# FPGA.net
KiCad netlist of a schematic drawn in Altium Designer
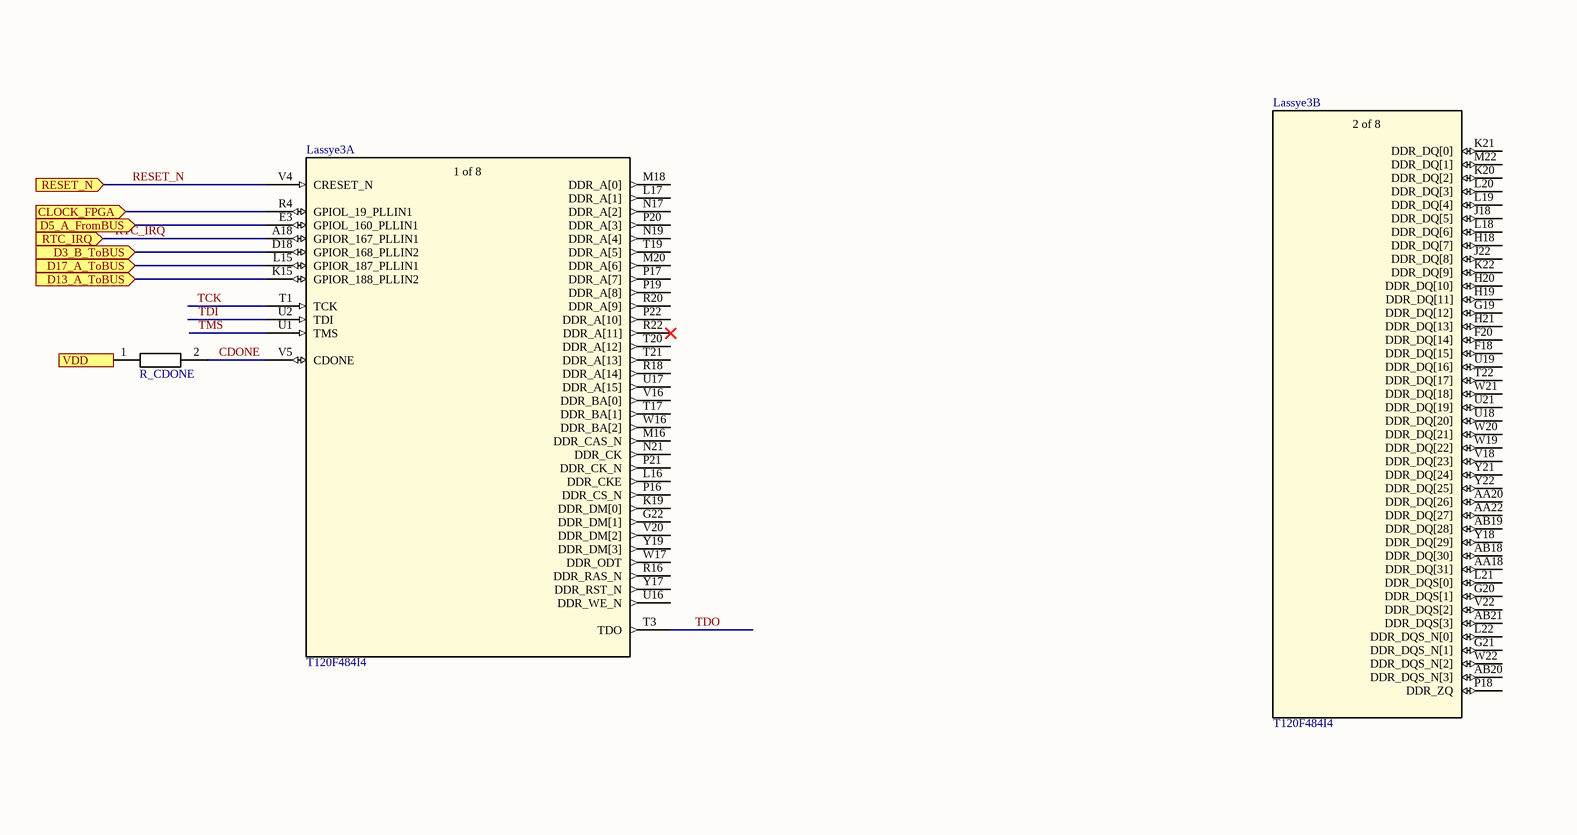
[diagram p0: FPGA.SchDoc, top left]
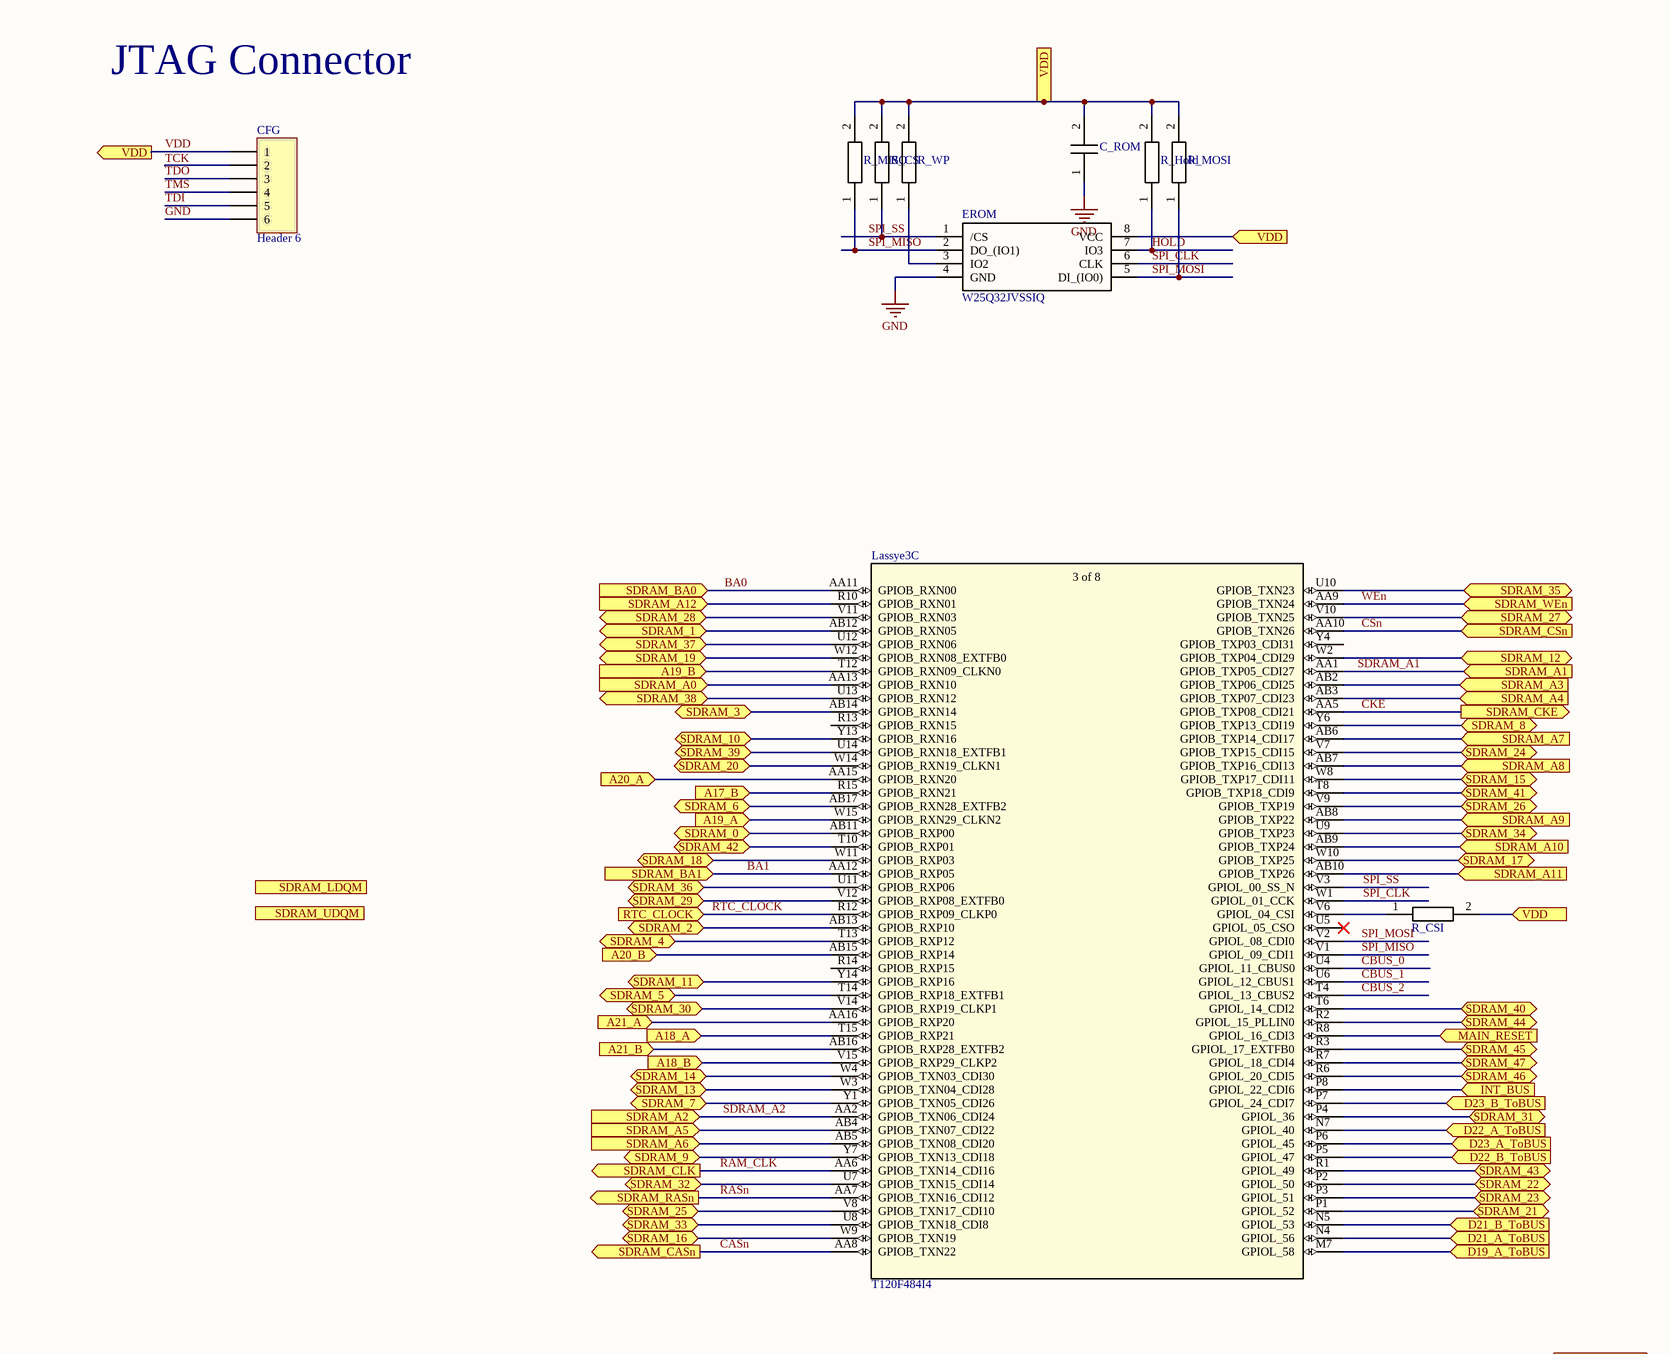
[diagram p1: FPGA.SchDoc, top middle]
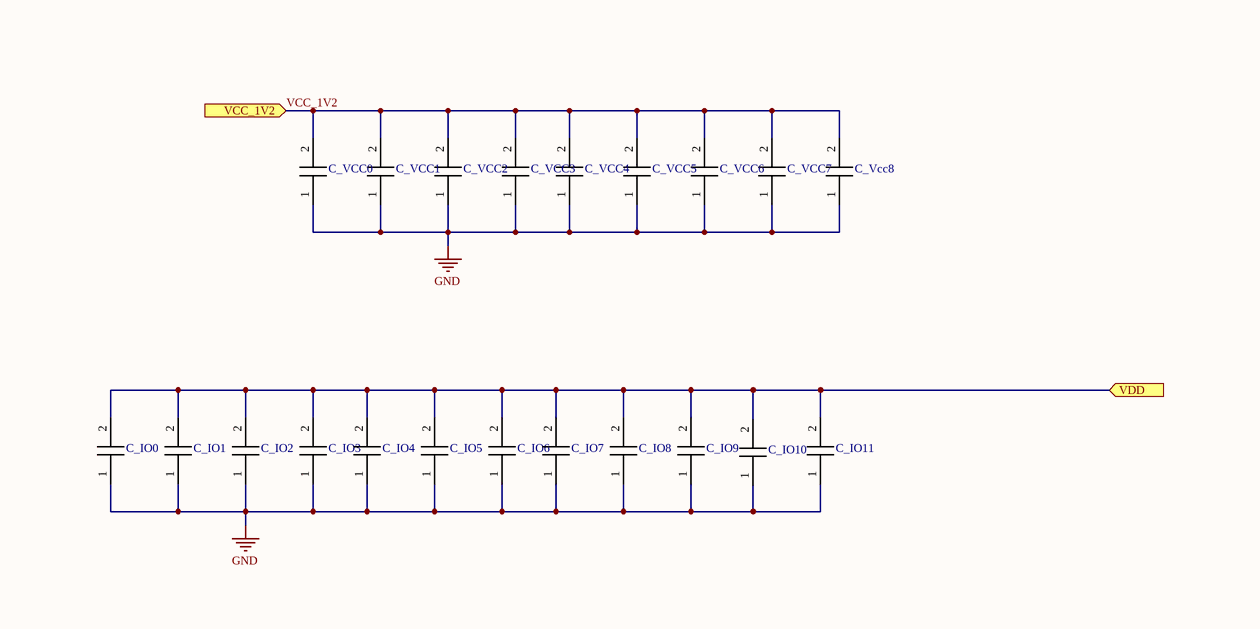
[diagram p2: FPGA.SchDoc, top right]
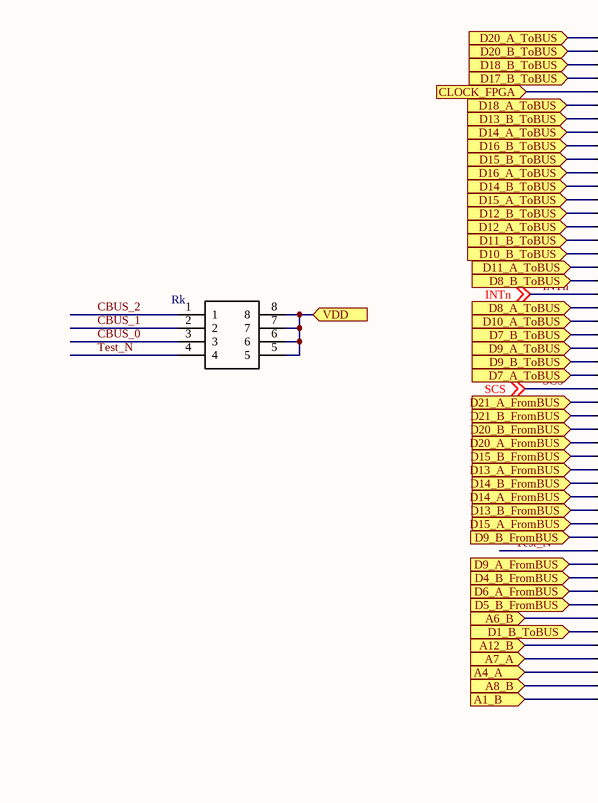
[diagram p3: FPGA.SchDoc, bottom middle]
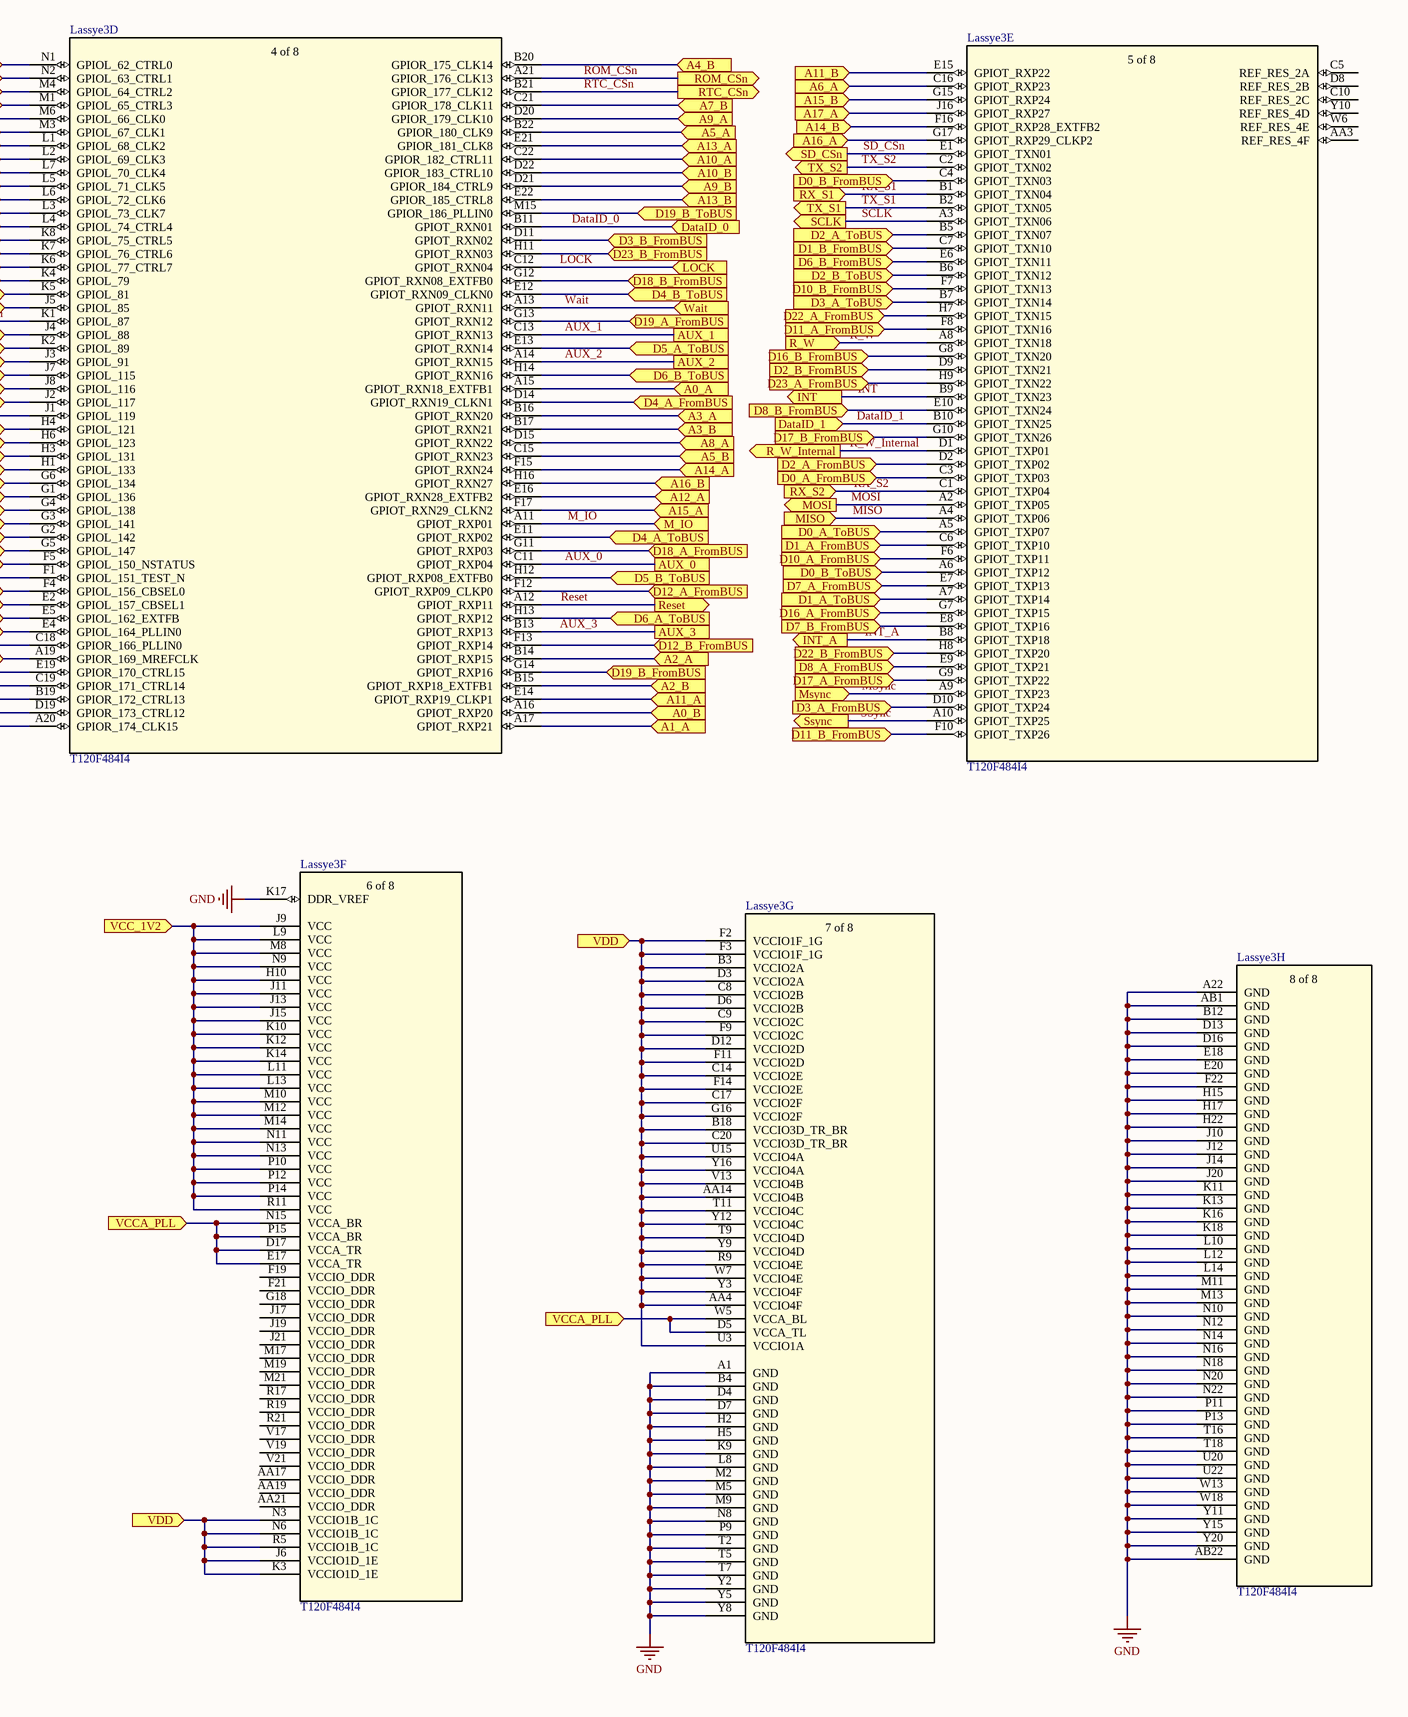
[diagram p4: FPGA.SchDoc, bottom right]

(export (version "E")
  (design (tool "Eeschema 10.0.6"))
  (components
    (comp (ref "CFG")
      (value "Header 6")
      (footprint "HDR1X6")
      (description "Header, 6-Pin")
      (fields (field (name "PUBLISHER") "Altium Limited"))
      (libsource (lib "Miscellaneous Connectors") (part "Header 6"))
    )
    (comp (ref "C_IO0")
      (value "GRM155R71C104JA88J")
      (footprint "SamacSys:CAPC1005X55N")
      (description "Capacitor")
      (fields (field (name "MOUSER PART NUMBER") "81-GRM155R71C104JA8J"))
      (libsource (lib "*") (part "GRM155R71C104JA88J"))
    )
    (comp (ref "C_IO1")
      (value "GRM155R71C104JA88J")
      (footprint "SamacSys:CAPC1005X55N")
      (description "Capacitor")
      (fields (field (name "MOUSER PART NUMBER") "81-GRM155R71C104JA8J"))
      (libsource (lib "*") (part "GRM155R71C104JA88J"))
    )
    (comp (ref "C_IO2")
      (value "GRM155R71C104JA88J")
      (footprint "SamacSys:CAPC1005X55N")
      (description "Capacitor")
      (fields (field (name "MOUSER PART NUMBER") "81-GRM155R71C104JA8J"))
      (libsource (lib "*") (part "GRM155R71C104JA88J"))
    )
    (comp (ref "C_IO3")
      (value "GRM155R71C104JA88J")
      (footprint "SamacSys:CAPC1005X55N")
      (description "Capacitor")
      (fields (field (name "MOUSER PART NUMBER") "81-GRM155R71C104JA8J"))
      (libsource (lib "*") (part "GRM155R71C104JA88J"))
    )
    (comp (ref "C_IO4")
      (value "GRM155R71C104JA88J")
      (footprint "SamacSys:CAPC1005X55N")
      (description "Capacitor")
      (fields (field (name "MOUSER PART NUMBER") "81-GRM155R71C104JA8J"))
      (libsource (lib "*") (part "GRM155R71C104JA88J"))
    )
    (comp (ref "C_IO5")
      (value "GRM155R71C104JA88J")
      (footprint "SamacSys:CAPC1005X55N")
      (description "Capacitor")
      (fields (field (name "MOUSER PART NUMBER") "81-GRM155R71C104JA8J"))
      (libsource (lib "*") (part "GRM155R71C104JA88J"))
    )
    (comp (ref "C_IO6")
      (value "GRM155R71C104JA88J")
      (footprint "SamacSys:CAPC1005X55N")
      (description "Capacitor")
      (fields (field (name "MOUSER PART NUMBER") "81-GRM155R71C104JA8J"))
      (libsource (lib "*") (part "GRM155R71C104JA88J"))
    )
    (comp (ref "C_IO7")
      (value "GRM155R71C104JA88J")
      (footprint "SamacSys:CAPC1005X55N")
      (description "Capacitor")
      (fields (field (name "MOUSER PART NUMBER") "81-GRM155R71C104JA8J"))
      (libsource (lib "*") (part "GRM155R71C104JA88J"))
    )
    (comp (ref "C_IO8")
      (value "GRM155R71C104JA88J")
      (footprint "SamacSys:CAPC1005X55N")
      (description "Capacitor")
      (fields (field (name "MOUSER PART NUMBER") "81-GRM155R71C104JA8J"))
      (libsource (lib "*") (part "GRM155R71C104JA88J"))
    )
    (comp (ref "C_IO9")
      (value "GRM155R71C104JA88J")
      (footprint "SamacSys:CAPC1005X55N")
      (description "Capacitor")
      (fields (field (name "MOUSER PART NUMBER") "81-GRM155R71C104JA8J"))
      (libsource (lib "*") (part "GRM155R71C104JA88J"))
    )
    (comp (ref "C_IO10")
      (value "GRM155R71C104JA88J")
      (footprint "SamacSys:CAPC1005X55N")
      (description "Capacitor")
      (fields (field (name "MOUSER PART NUMBER") "81-GRM155R71C104JA8J"))
      (libsource (lib "*") (part "GRM155R71C104JA88J"))
    )
    (comp (ref "C_IO11")
      (value "GRM155R71C104JA88J")
      (footprint "SamacSys:CAPC1005X55N")
      (description "Capacitor")
      (fields (field (name "MOUSER PART NUMBER") "81-GRM155R71C104JA8J"))
      (libsource (lib "*") (part "GRM155R71C104JA88J"))
    )
    (comp (ref "C_ROM")
      (value "0603YC104K4T2A")
      (footprint "SamacSys:CAPC1608X90N")
      (description "Capacitor")
      (fields (field (name "MOUSER PART NUMBER") "581-0603YC104K4"))
      (libsource (lib "*") (part "0603YC104K4T2A"))
    )
    (comp (ref "C_VCC0")
      (value "GRM155R71C104JA88J")
      (footprint "SamacSys:CAPC1005X55N")
      (description "Capacitor")
      (fields (field (name "MOUSER PART NUMBER") "81-GRM155R71C104JA8J"))
      (libsource (lib "*") (part "GRM155R71C104JA88J"))
    )
    (comp (ref "C_VCC1")
      (value "GRM155R71C104JA88J")
      (footprint "SamacSys:CAPC1005X55N")
      (description "Capacitor")
      (fields (field (name "MOUSER PART NUMBER") "81-GRM155R71C104JA8J"))
      (libsource (lib "*") (part "GRM155R71C104JA88J"))
    )
    (comp (ref "C_VCC2")
      (value "GRM155R71C104JA88J")
      (footprint "SamacSys:CAPC1005X55N")
      (description "Capacitor")
      (fields (field (name "MOUSER PART NUMBER") "81-GRM155R71C104JA8J"))
      (libsource (lib "*") (part "GRM155R71C104JA88J"))
    )
    (comp (ref "C_VCC3")
      (value "GRM155R71C104JA88J")
      (footprint "SamacSys:CAPC1005X55N")
      (description "Capacitor")
      (fields (field (name "MOUSER PART NUMBER") "81-GRM155R71C104JA8J"))
      (libsource (lib "*") (part "GRM155R71C104JA88J"))
    )
    (comp (ref "C_VCC4")
      (value "GRM155R71C104JA88J")
      (footprint "SamacSys:CAPC1005X55N")
      (description "Capacitor")
      (fields (field (name "MOUSER PART NUMBER") "81-GRM155R71C104JA8J"))
      (libsource (lib "*") (part "GRM155R71C104JA88J"))
    )
    (comp (ref "C_VCC5")
      (value "GRM155R71C104JA88J")
      (footprint "SamacSys:CAPC1005X55N")
      (description "Capacitor")
      (fields (field (name "MOUSER PART NUMBER") "81-GRM155R71C104JA8J"))
      (libsource (lib "*") (part "GRM155R71C104JA88J"))
    )
    (comp (ref "C_VCC6")
      (value "GRM155R71C104JA88J")
      (footprint "SamacSys:CAPC1005X55N")
      (description "Capacitor")
      (fields (field (name "MOUSER PART NUMBER") "81-GRM155R71C104JA8J"))
      (libsource (lib "*") (part "GRM155R71C104JA88J"))
    )
    (comp (ref "C_VCC7")
      (value "GRM155R71C104JA88J")
      (footprint "SamacSys:CAPC1005X55N")
      (description "Capacitor")
      (fields (field (name "MOUSER PART NUMBER") "81-GRM155R71C104JA8J"))
      (libsource (lib "*") (part "GRM155R71C104JA88J"))
    )
    (comp (ref "C_Vcc8")
      (value "GRM155R71C104JA88J")
      (footprint "SamacSys:CAPC1005X55N")
      (description "Capacitor")
      (fields (field (name "MOUSER PART NUMBER") "81-GRM155R71C104JA8J"))
      (libsource (lib "*") (part "GRM155R71C104JA88J"))
    )
    (comp (ref "EROM")
      (value "W25Q32JVSSIQ")
      (footprint "SamacSys:SOIC127P790X216-8N")
      (description "Integrated Circuit")
      (fields (field (name "MOUSER PART NUMBER") "454-W25Q32JVSSIQ"))
      (libsource (lib "*") (part "W25Q32JVSSIQ"))
    )
    (comp (ref "Lassye3")
      (value "T120F484I4")
      (footprint "FBGA484_TRION_EFI")
      (description "No Description Available")
      (libsource (lib "T120F484I4") (part "T120F484I4"))
    )
    (comp (ref "Rk")
      (value "CAT16A-1002F4LF")
      (footprint "SamacSys:CAT16A1002F4LF")
      (description "Resistor Network")
      (fields (field (name "MOUSER PART NUMBER") "652-CAT16A-1002F4LF"))
      (libsource (lib "*") (part "CAT16A-1002F4LF"))
    )
    (comp (ref "R_CDONE")
      (value "CRCW060310K0FKEB")
      (footprint "SamacSys:RESC1608X50N")
      (description "Resistor")
      (fields (field (name "MOUSER PART NUMBER") "71-CRCW060310K0FKEB"))
      (libsource (lib "*") (part "CRCW060310K0FKEB"))
    )
    (comp (ref "R_CS")
      (value "CRCW060310K0FKEB")
      (footprint "SamacSys:RESC1608X50N")
      (description "Resistor")
      (fields (field (name "MOUSER PART NUMBER") "71-CRCW060310K0FKEB"))
      (libsource (lib "*") (part "CRCW060310K0FKEB"))
    )
    (comp (ref "R_CSI")
      (value "CRCW060310K0FKEB")
      (footprint "SamacSys:RESC1608X50N")
      (description "Resistor")
      (fields (field (name "MOUSER PART NUMBER") "71-CRCW060310K0FKEB"))
      (libsource (lib "*") (part "CRCW060310K0FKEB"))
    )
    (comp (ref "R_Hold")
      (value "CRCW060310K0FKEB")
      (footprint "SamacSys:RESC1608X50N")
      (description "Resistor")
      (fields (field (name "MOUSER PART NUMBER") "71-CRCW060310K0FKEB"))
      (libsource (lib "*") (part "CRCW060310K0FKEB"))
    )
    (comp (ref "R_MISO")
      (value "CRCW060310K0FKEB")
      (footprint "SamacSys:RESC1608X50N")
      (description "Resistor")
      (fields (field (name "MOUSER PART NUMBER") "71-CRCW060310K0FKEB"))
      (libsource (lib "*") (part "CRCW060310K0FKEB"))
    )
    (comp (ref "R_MOSI")
      (value "CRCW060310K0FKEB")
      (footprint "SamacSys:RESC1608X50N")
      (description "Resistor")
      (fields (field (name "MOUSER PART NUMBER") "71-CRCW060310K0FKEB"))
      (libsource (lib "*") (part "CRCW060310K0FKEB"))
    )
    (comp (ref "R_WP")
      (value "CRCW060310K0FKEB")
      (footprint "SamacSys:RESC1608X50N")
      (description "Resistor")
      (fields (field (name "MOUSER PART NUMBER") "71-CRCW060310K0FKEB"))
      (libsource (lib "*") (part "CRCW060310K0FKEB"))
    )
  )
  (nets
    (net (code "1") (name "/A0_A") (class "Default")
      (node (ref "Lassye3") (pin "A15") (pinfunction "GPIOT_RXN18_EXTFB1_A15") (pintype "bidirectional"))
    )
    (net (code "2") (name "/A0_B") (class "Default")
      (node (ref "Lassye3") (pin "A16") (pinfunction "GPIOT_RXP20_A16") (pintype "bidirectional"))
    )
    (net (code "3") (name "/A1_A") (class "Default")
      (node (ref "Lassye3") (pin "A17") (pinfunction "GPIOT_RXP21_A17") (pintype "bidirectional"))
    )
    (net (code "4") (name "/A1_B") (class "Default")
      (node (ref "Lassye3") (pin "A20") (pinfunction "GPIOR_174_CLK15_A20") (pintype "bidirectional"))
    )
    (net (code "5") (name "/A2_A") (class "Default")
      (node (ref "Lassye3") (pin "B14") (pinfunction "GPIOT_RXP15_B14") (pintype "bidirectional"))
    )
    (net (code "6") (name "/A2_B") (class "Default")
      (node (ref "Lassye3") (pin "B15") (pinfunction "GPIOT_RXP18_EXTFB1_B15") (pintype "bidirectional"))
    )
    (net (code "7") (name "/A3_A") (class "Default")
      (node (ref "Lassye3") (pin "B16") (pinfunction "GPIOT_RXN20_B16") (pintype "bidirectional"))
    )
    (net (code "8") (name "/A3_B") (class "Default")
      (node (ref "Lassye3") (pin "B17") (pinfunction "GPIOT_RXN21_B17") (pintype "bidirectional"))
    )
    (net (code "9") (name "/A4_A") (class "Default")
      (node (ref "Lassye3") (pin "B19") (pinfunction "GPIOR_172_CTRL13_B19") (pintype "bidirectional"))
    )
    (net (code "10") (name "/A4_B") (class "Default")
      (node (ref "Lassye3") (pin "B20") (pinfunction "GPIOR_175_CLK14_B20") (pintype "bidirectional"))
    )
    (net (code "11") (name "/A5_A") (class "Default")
      (node (ref "Lassye3") (pin "B22") (pinfunction "GPIOR_180_CLK9_B22") (pintype "bidirectional"))
    )
    (net (code "12") (name "/A5_B") (class "Default")
      (node (ref "Lassye3") (pin "C15") (pinfunction "GPIOT_RXN23_C15") (pintype "bidirectional"))
    )
    (net (code "13") (name "/A6_A") (class "Default")
      (node (ref "Lassye3") (pin "C16") (pinfunction "GPIOT_RXP23_C16") (pintype "bidirectional"))
    )
    (net (code "14") (name "/A6_B") (class "Default")
      (node (ref "Lassye3") (pin "C18") (pinfunction "GPIOR_166_PLLIN0_C18") (pintype "bidirectional"))
    )
    (net (code "15") (name "/A7_A") (class "Default")
      (node (ref "Lassye3") (pin "C19") (pinfunction "GPIOR_171_CTRL14_C19") (pintype "bidirectional"))
    )
    (net (code "16") (name "/A7_B") (class "Default")
      (node (ref "Lassye3") (pin "C21") (pinfunction "GPIOR_178_CLK11_C21") (pintype "bidirectional"))
    )
    (net (code "17") (name "/A8_A") (class "Default")
      (node (ref "Lassye3") (pin "D15") (pinfunction "GPIOT_RXN22_D15") (pintype "bidirectional"))
    )
    (net (code "18") (name "/A8_B") (class "Default")
      (node (ref "Lassye3") (pin "D19") (pinfunction "GPIOR_173_CTRL12_D19") (pintype "bidirectional"))
    )
    (net (code "19") (name "/A9_A") (class "Default")
      (node (ref "Lassye3") (pin "D20") (pinfunction "GPIOR_179_CLK10_D20") (pintype "bidirectional"))
    )
    (net (code "20") (name "/A9_B") (class "Default")
      (node (ref "Lassye3") (pin "D21") (pinfunction "GPIOR_184_CTRL9_D21") (pintype "bidirectional"))
    )
    (net (code "21") (name "/A10_A") (class "Default")
      (node (ref "Lassye3") (pin "C22") (pinfunction "GPIOR_182_CTRL11_C22") (pintype "bidirectional"))
    )
    (net (code "22") (name "/A10_B") (class "Default")
      (node (ref "Lassye3") (pin "D22") (pinfunction "GPIOR_183_CTRL10_D22") (pintype "bidirectional"))
    )
    (net (code "23") (name "/A11_A") (class "Default")
      (node (ref "Lassye3") (pin "E14") (pinfunction "GPIOT_RXP19_CLKP1_E14") (pintype "bidirectional"))
    )
    (net (code "24") (name "/A11_B") (class "Default")
      (node (ref "Lassye3") (pin "E15") (pinfunction "GPIOT_RXP22_E15") (pintype "bidirectional"))
    )
    (net (code "25") (name "/A12_A") (class "Default")
      (node (ref "Lassye3") (pin "E16") (pinfunction "GPIOT_RXN28_EXTFB2_E16") (pintype "bidirectional"))
    )
    (net (code "26") (name "/A12_B") (class "Default")
      (node (ref "Lassye3") (pin "E19") (pinfunction "GPIOR_170_CTRL15_E19") (pintype "bidirectional"))
    )
    (net (code "27") (name "/A13_A") (class "Default")
      (node (ref "Lassye3") (pin "E21") (pinfunction "GPIOR_181_CLK8_E21") (pintype "bidirectional"))
    )
    (net (code "28") (name "/A13_B") (class "Default")
      (node (ref "Lassye3") (pin "E22") (pinfunction "GPIOR_185_CTRL8_E22") (pintype "bidirectional"))
    )
    (net (code "29") (name "/A14_A") (class "Default")
      (node (ref "Lassye3") (pin "F15") (pinfunction "GPIOT_RXN24_F15") (pintype "bidirectional"))
    )
    (net (code "30") (name "/A14_B") (class "Default")
      (node (ref "Lassye3") (pin "F16") (pinfunction "GPIOT_RXP28_EXTFB2_F16") (pintype "bidirectional"))
    )
    (net (code "31") (name "/A15_A") (class "Default")
      (node (ref "Lassye3") (pin "F17") (pinfunction "GPIOT_RXN29_CLKN2_F17") (pintype "bidirectional"))
    )
    (net (code "32") (name "/A15_B") (class "Default")
      (node (ref "Lassye3") (pin "G15") (pinfunction "GPIOT_RXP24_G15") (pintype "bidirectional"))
    )
    (net (code "33") (name "/A16_A") (class "Default")
      (node (ref "Lassye3") (pin "G17") (pinfunction "GPIOT_RXP29_CLKP2_G17") (pintype "bidirectional"))
    )
    (net (code "34") (name "/A16_B") (class "Default")
      (node (ref "Lassye3") (pin "H16") (pinfunction "GPIOT_RXN27_H16") (pintype "bidirectional"))
    )
    (net (code "35") (name "/A17_A") (class "Default")
      (node (ref "Lassye3") (pin "J16") (pinfunction "GPIOT_RXP27_J16") (pintype "bidirectional"))
    )
    (net (code "36") (name "/A17_B") (class "Default")
      (node (ref "Lassye3") (pin "R15") (pinfunction "GPIOB_RXN21_R15") (pintype "bidirectional"))
    )
    (net (code "37") (name "/A18_A") (class "Default")
      (node (ref "Lassye3") (pin "T15") (pinfunction "GPIOB_RXP21_T15") (pintype "bidirectional"))
    )
    (net (code "38") (name "/A18_B") (class "Default")
      (node (ref "Lassye3") (pin "V15") (pinfunction "GPIOB_RXP29_CLKP2_V15") (pintype "bidirectional"))
    )
    (net (code "39") (name "/A19_A") (class "Default")
      (node (ref "Lassye3") (pin "W15") (pinfunction "GPIOB_RXN29_CLKN2_W15") (pintype "bidirectional"))
    )
    (net (code "40") (name "/A19_B") (class "Default")
      (node (ref "Lassye3") (pin "T12") (pinfunction "GPIOB_RXN09_CLKN0_T12") (pintype "bidirectional"))
    )
    (net (code "41") (name "/A20_A") (class "Default")
      (node (ref "Lassye3") (pin "AA15") (pinfunction "GPIOB_RXN20_AA15") (pintype "bidirectional"))
    )
    (net (code "42") (name "/A20_B") (class "Default")
      (node (ref "Lassye3") (pin "AB15") (pinfunction "GPIOB_RXP14_AB15") (pintype "bidirectional"))
    )
    (net (code "43") (name "/A21_A") (class "Default")
      (node (ref "Lassye3") (pin "AA16") (pinfunction "GPIOB_RXP20_AA16") (pintype "bidirectional"))
    )
    (net (code "44") (name "/A21_B") (class "Default")
      (node (ref "Lassye3") (pin "AB16") (pinfunction "GPIOB_RXP28_EXTFB2_AB16") (pintype "bidirectional"))
    )
    (net (code "45") (name "/AUX_0") (class "Default")
      (node (ref "Lassye3") (pin "C11") (pinfunction "GPIOT_RXP04_C11") (pintype "bidirectional"))
    )
    (net (code "46") (name "/AUX_1") (class "Default")
      (node (ref "Lassye3") (pin "C13") (pinfunction "GPIOT_RXN13_C13") (pintype "bidirectional"))
    )
    (net (code "47") (name "/AUX_2") (class "Default")
      (node (ref "Lassye3") (pin "A14") (pinfunction "GPIOT_RXN15_A14") (pintype "bidirectional"))
    )
    (net (code "48") (name "/AUX_3") (class "Default")
      (node (ref "Lassye3") (pin "B13") (pinfunction "GPIOT_RXP13_B13") (pintype "bidirectional"))
    )
    (net (code "49") (name "/BA0") (class "Default")
      (node (ref "Lassye3") (pin "AA11") (pinfunction "GPIOB_RXN00_AA11") (pintype "bidirectional"))
    )
    (net (code "50") (name "/BA1") (class "Default")
      (node (ref "Lassye3") (pin "AA12") (pinfunction "GPIOB_RXP05_AA12") (pintype "bidirectional"))
    )
    (net (code "51") (name "/CASn") (class "Default")
      (node (ref "Lassye3") (pin "AA8") (pinfunction "GPIOB_TXN22_AA8") (pintype "bidirectional"))
    )
    (net (code "52") (name "/CBUS_0") (class "Default")
      (node (ref "Lassye3") (pin "U4") (pinfunction "GPIOL_11_CBUS0_U4") (pintype "bidirectional"))
      (node (ref "Rk") (pin "3") (pinfunction "3_3") (pintype "passive"))
    )
    (net (code "53") (name "/CBUS_1") (class "Default")
      (node (ref "Lassye3") (pin "U6") (pinfunction "GPIOL_12_CBUS1_U6") (pintype "bidirectional"))
      (node (ref "Rk") (pin "2") (pinfunction "2_2") (pintype "passive"))
    )
    (net (code "54") (name "/CBUS_2") (class "Default")
      (node (ref "Lassye3") (pin "T4") (pinfunction "GPIOL_13_CBUS2_T4") (pintype "bidirectional"))
      (node (ref "Rk") (pin "1") (pinfunction "1_1") (pintype "passive"))
    )
    (net (code "55") (name "/CDONE") (class "Default")
      (node (ref "Lassye3") (pin "V5") (pinfunction "CDONE_V5") (pintype "bidirectional"))
      (node (ref "R_CDONE") (pin "2") (pinfunction "2_2") (pintype "passive"))
    )
    (net (code "56") (name "/CKE") (class "Default")
      (node (ref "Lassye3") (pin "AA5") (pinfunction "GPIOB_TXP08_CDI21_AA5") (pintype "bidirectional"))
    )
    (net (code "57") (name "/CLOCK_FPGA") (class "Default")
      (node (ref "Lassye3") (pin "M6") (pinfunction "GPIOL_66_CLK0_M6") (pintype "bidirectional"))
      (node (ref "Lassye3") (pin "R4") (pinfunction "GPIOL_19_PLLIN1_R4") (pintype "bidirectional"))
    )
    (net (code "58") (name "/CSn") (class "Default")
      (node (ref "Lassye3") (pin "AA10") (pinfunction "GPIOB_TXN26_AA10") (pintype "bidirectional"))
    )
    (net (code "59") (name "/D0_A_FromBUS") (class "Default")
      (node (ref "Lassye3") (pin "C3") (pinfunction "GPIOT_TXP03_C3") (pintype "bidirectional"))
    )
    (net (code "60") (name "/D0_A_ToBUS") (class "Default")
      (node (ref "Lassye3") (pin "A5") (pinfunction "GPIOT_TXP07_A5") (pintype "bidirectional"))
    )
    (net (code "61") (name "/D0_B_FromBUS") (class "Default")
      (node (ref "Lassye3") (pin "C4") (pinfunction "GPIOT_TXN03_C4") (pintype "bidirectional"))
    )
    (net (code "62") (name "/D0_B_ToBUS") (class "Default")
      (node (ref "Lassye3") (pin "A6") (pinfunction "GPIOT_TXP12_A6") (pintype "bidirectional"))
    )
    (net (code "63") (name "/D1_A_FromBUS") (class "Default")
      (node (ref "Lassye3") (pin "C6") (pinfunction "GPIOT_TXP10_C6") (pintype "bidirectional"))
    )
    (net (code "64") (name "/D1_A_ToBUS") (class "Default")
      (node (ref "Lassye3") (pin "A7") (pinfunction "GPIOT_TXP14_A7") (pintype "bidirectional"))
    )
    (net (code "65") (name "/D1_B_FromBUS") (class "Default")
      (node (ref "Lassye3") (pin "C7") (pinfunction "GPIOT_TXN10_C7") (pintype "bidirectional"))
    )
    (net (code "66") (name "/D1_B_ToBUS") (class "Default")
      (node (ref "Lassye3") (pin "A19") (pinfunction "GPIOR_169_MREFCLK_A19") (pintype "bidirectional"))
    )
    (net (code "67") (name "/D2_A_FromBUS") (class "Default")
      (node (ref "Lassye3") (pin "D2") (pinfunction "GPIOT_TXP02_D2") (pintype "bidirectional"))
    )
    (net (code "68") (name "/D2_A_ToBUS") (class "Default")
      (node (ref "Lassye3") (pin "B5") (pinfunction "GPIOT_TXN07_B5") (pintype "bidirectional"))
    )
    (net (code "69") (name "/D2_B_FromBUS") (class "Default")
      (node (ref "Lassye3") (pin "D9") (pinfunction "GPIOT_TXN21_D9") (pintype "bidirectional"))
    )
    (net (code "70") (name "/D2_B_ToBUS") (class "Default")
      (node (ref "Lassye3") (pin "B6") (pinfunction "GPIOT_TXN12_B6") (pintype "bidirectional"))
    )
    (net (code "71") (name "/D3_A_FromBUS") (class "Default")
      (node (ref "Lassye3") (pin "D10") (pinfunction "GPIOT_TXP24_D10") (pintype "bidirectional"))
    )
    (net (code "72") (name "/D3_A_ToBUS") (class "Default")
      (node (ref "Lassye3") (pin "B7") (pinfunction "GPIOT_TXN14_B7") (pintype "bidirectional"))
    )
    (net (code "73") (name "/D3_B_FromBUS") (class "Default")
      (node (ref "Lassye3") (pin "D11") (pinfunction "GPIOT_RXN02_D11") (pintype "bidirectional"))
    )
    (net (code "74") (name "/D3_B_ToBUS") (class "Default")
      (node (ref "Lassye3") (pin "D18") (pinfunction "GPIOR_168_PLLIN2_D18") (pintype "bidirectional"))
    )
    (net (code "75") (name "/D4_A_FromBUS") (class "Default")
      (node (ref "Lassye3") (pin "D14") (pinfunction "GPIOT_RXN19_CLKN1_D14") (pintype "bidirectional"))
    )
    (net (code "76") (name "/D4_A_ToBUS") (class "Default")
      (node (ref "Lassye3") (pin "E11") (pinfunction "GPIOT_RXP02_E11") (pintype "bidirectional"))
    )
    (net (code "77") (name "/D4_B_FromBUS") (class "Default")
      (node (ref "Lassye3") (pin "E2") (pinfunction "GPIOL_157_CBSEL1_E2") (pintype "bidirectional"))
    )
    (net (code "78") (name "/D4_B_ToBUS") (class "Default")
      (node (ref "Lassye3") (pin "E12") (pinfunction "GPIOT_RXN09_CLKN0_E12") (pintype "bidirectional"))
    )
    (net (code "79") (name "/D5_A_FromBUS") (class "Default")
      (node (ref "Lassye3") (pin "E3") (pinfunction "GPIOL_160_PLLIN1_E3") (pintype "bidirectional"))
    )
    (net (code "80") (name "/D5_A_ToBUS") (class "Default")
      (node (ref "Lassye3") (pin "E13") (pinfunction "GPIOT_RXN14_E13") (pintype "bidirectional"))
    )
    (net (code "81") (name "/D5_B_FromBUS") (class "Default")
      (node (ref "Lassye3") (pin "E4") (pinfunction "GPIOL_164_PLLIN0_E4") (pintype "bidirectional"))
    )
    (net (code "82") (name "/D5_B_ToBUS") (class "Default")
      (node (ref "Lassye3") (pin "H12") (pinfunction "GPIOT_RXP08_EXTFB0_H12") (pintype "bidirectional"))
    )
    (net (code "83") (name "/D6_A_FromBUS") (class "Default")
      (node (ref "Lassye3") (pin "E5") (pinfunction "GPIOL_162_EXTFB_E5") (pintype "bidirectional"))
    )
    (net (code "84") (name "/D6_A_ToBUS") (class "Default")
      (node (ref "Lassye3") (pin "H13") (pinfunction "GPIOT_RXP12_H13") (pintype "bidirectional"))
    )
    (net (code "85") (name "/D6_B_FromBUS") (class "Default")
      (node (ref "Lassye3") (pin "E6") (pinfunction "GPIOT_TXN11_E6") (pintype "bidirectional"))
    )
    (net (code "86") (name "/D6_B_ToBUS") (class "Default")
      (node (ref "Lassye3") (pin "H14") (pinfunction "GPIOT_RXN16_H14") (pintype "bidirectional"))
    )
    (net (code "87") (name "/D7_A_FromBUS") (class "Default")
      (node (ref "Lassye3") (pin "E7") (pinfunction "GPIOT_TXP13_E7") (pintype "bidirectional"))
    )
    (net (code "88") (name "/D7_A_ToBUS") (class "Default")
      (node (ref "Lassye3") (pin "J2") (pinfunction "GPIOL_117_J2") (pintype "bidirectional"))
    )
    (net (code "89") (name "/D7_B_FromBUS") (class "Default")
      (node (ref "Lassye3") (pin "E8") (pinfunction "GPIOT_TXP16_E8") (pintype "bidirectional"))
    )
    (net (code "90") (name "/D7_B_ToBUS") (class "Default")
      (node (ref "Lassye3") (pin "J3") (pinfunction "GPIOL_91_J3") (pintype "bidirectional"))
    )
    (net (code "91") (name "/D8_A_FromBUS") (class "Default")
      (node (ref "Lassye3") (pin "E9") (pinfunction "GPIOT_TXP21_E9") (pintype "bidirectional"))
    )
    (net (code "92") (name "/D8_A_ToBUS") (class "Default")
      (node (ref "Lassye3") (pin "J4") (pinfunction "GPIOL_88_J4") (pintype "bidirectional"))
    )
    (net (code "93") (name "/D8_B_FromBUS") (class "Default")
      (node (ref "Lassye3") (pin "E10") (pinfunction "GPIOT_TXN24_E10") (pintype "bidirectional"))
    )
    (net (code "94") (name "/D8_B_ToBUS") (class "Default")
      (node (ref "Lassye3") (pin "J5") (pinfunction "GPIOL_85_J5") (pintype "bidirectional"))
    )
    (net (code "95") (name "/D9_A_FromBUS") (class "Default")
      (node (ref "Lassye3") (pin "F4") (pinfunction "GPIOL_156_CBSEL0_F4") (pintype "bidirectional"))
    )
    (net (code "96") (name "/D9_A_ToBUS") (class "Default")
      (node (ref "Lassye3") (pin "J7") (pinfunction "GPIOL_115_J7") (pintype "bidirectional"))
    )
    (net (code "97") (name "/D9_B_FromBUS") (class "Default")
      (node (ref "Lassye3") (pin "F5") (pinfunction "GPIOL_150_NSTATUS_F5") (pintype "bidirectional"))
    )
    (net (code "98") (name "/D9_B_ToBUS") (class "Default")
      (node (ref "Lassye3") (pin "J8") (pinfunction "GPIOL_116_J8") (pintype "bidirectional"))
    )
    (net (code "99") (name "/D10_A_FromBUS") (class "Default")
      (node (ref "Lassye3") (pin "F6") (pinfunction "GPIOT_TXP11_F6") (pintype "bidirectional"))
    )
    (net (code "100") (name "/D10_A_ToBUS") (class "Default")
      (node (ref "Lassye3") (pin "K2") (pinfunction "GPIOL_89_K2") (pintype "bidirectional"))
    )
    (net (code "101") (name "/D10_B_FromBUS") (class "Default")
      (node (ref "Lassye3") (pin "F7") (pinfunction "GPIOT_TXN13_F7") (pintype "bidirectional"))
    )
    (net (code "102") (name "/D10_B_ToBUS") (class "Default")
      (node (ref "Lassye3") (pin "K4") (pinfunction "GPIOL_79_K4") (pintype "bidirectional"))
    )
    (net (code "103") (name "/D11_A_FromBUS") (class "Default")
      (node (ref "Lassye3") (pin "F8") (pinfunction "GPIOT_TXN16_F8") (pintype "bidirectional"))
    )
    (net (code "104") (name "/D11_A_ToBUS") (class "Default")
      (node (ref "Lassye3") (pin "K5") (pinfunction "GPIOL_81_K5") (pintype "bidirectional"))
    )
    (net (code "105") (name "/D11_B_FromBUS") (class "Default")
      (node (ref "Lassye3") (pin "F10") (pinfunction "GPIOT_TXP26_F10") (pintype "bidirectional"))
    )
    (net (code "106") (name "/D11_B_ToBUS") (class "Default")
      (node (ref "Lassye3") (pin "K6") (pinfunction "GPIOL_77_CTRL7_K6") (pintype "bidirectional"))
    )
    (net (code "107") (name "/D12_A_FromBUS") (class "Default")
      (node (ref "Lassye3") (pin "F12") (pinfunction "GPIOT_RXP09_CLKP0_F12") (pintype "bidirectional"))
    )
    (net (code "108") (name "/D12_A_ToBUS") (class "Default")
      (node (ref "Lassye3") (pin "K7") (pinfunction "GPIOL_76_CTRL6_K7") (pintype "bidirectional"))
    )
    (net (code "109") (name "/D12_B_FromBUS") (class "Default")
      (node (ref "Lassye3") (pin "F13") (pinfunction "GPIOT_RXP14_F13") (pintype "bidirectional"))
    )
    (net (code "110") (name "/D12_B_ToBUS") (class "Default")
      (node (ref "Lassye3") (pin "K8") (pinfunction "GPIOL_75_CTRL5_K8") (pintype "bidirectional"))
    )
    (net (code "111") (name "/D13_A_FromBUS") (class "Default")
      (node (ref "Lassye3") (pin "G1") (pinfunction "GPIOL_136_G1") (pintype "bidirectional"))
    )
    (net (code "112") (name "/D13_A_ToBUS") (class "Default")
      (node (ref "Lassye3") (pin "K15") (pinfunction "GPIOR_188_PLLIN2_K15") (pintype "bidirectional"))
    )
    (net (code "113") (name "/D13_B_FromBUS") (class "Default")
      (node (ref "Lassye3") (pin "G2") (pinfunction "GPIOL_142_G2") (pintype "bidirectional"))
    )
    (net (code "114") (name "/D13_B_ToBUS") (class "Default")
      (node (ref "Lassye3") (pin "L1") (pinfunction "GPIOL_68_CLK2_L1") (pintype "bidirectional"))
    )
    (net (code "115") (name "/D14_A_FromBUS") (class "Default")
      (node (ref "Lassye3") (pin "G3") (pinfunction "GPIOL_141_G3") (pintype "bidirectional"))
    )
    (net (code "116") (name "/D14_A_ToBUS") (class "Default")
      (node (ref "Lassye3") (pin "L2") (pinfunction "GPIOL_69_CLK3_L2") (pintype "bidirectional"))
    )
    (net (code "117") (name "/D14_B_FromBUS") (class "Default")
      (node (ref "Lassye3") (pin "G4") (pinfunction "GPIOL_138_G4") (pintype "bidirectional"))
    )
    (net (code "118") (name "/D14_B_ToBUS") (class "Default")
      (node (ref "Lassye3") (pin "L3") (pinfunction "GPIOL_73_CLK7_L3") (pintype "bidirectional"))
    )
    (net (code "119") (name "/D15_A_FromBUS") (class "Default")
      (node (ref "Lassye3") (pin "G5") (pinfunction "GPIOL_147_G5") (pintype "bidirectional"))
    )
    (net (code "120") (name "/D15_A_ToBUS") (class "Default")
      (node (ref "Lassye3") (pin "L4") (pinfunction "GPIOL_74_CTRL4_L4") (pintype "bidirectional"))
    )
    (net (code "121") (name "/D15_B_FromBUS") (class "Default")
      (node (ref "Lassye3") (pin "G6") (pinfunction "GPIOL_134_G6") (pintype "bidirectional"))
    )
    (net (code "122") (name "/D15_B_ToBUS") (class "Default")
      (node (ref "Lassye3") (pin "L5") (pinfunction "GPIOL_71_CLK5_L5") (pintype "bidirectional"))
    )
    (net (code "123") (name "/D16_A_FromBUS") (class "Default")
      (node (ref "Lassye3") (pin "G7") (pinfunction "GPIOT_TXP15_G7") (pintype "bidirectional"))
    )
    (net (code "124") (name "/D16_A_ToBUS") (class "Default")
      (node (ref "Lassye3") (pin "L6") (pinfunction "GPIOL_72_CLK6_L6") (pintype "bidirectional"))
    )
    (net (code "125") (name "/D16_B_FromBUS") (class "Default")
      (node (ref "Lassye3") (pin "G8") (pinfunction "GPIOT_TXN20_G8") (pintype "bidirectional"))
    )
    (net (code "126") (name "/D16_B_ToBUS") (class "Default")
      (node (ref "Lassye3") (pin "L7") (pinfunction "GPIOL_70_CLK4_L7") (pintype "bidirectional"))
    )
    (net (code "127") (name "/D17_A_FromBUS") (class "Default")
      (node (ref "Lassye3") (pin "G9") (pinfunction "GPIOT_TXP22_G9") (pintype "bidirectional"))
    )
    (net (code "128") (name "/D17_A_ToBUS") (class "Default")
      (node (ref "Lassye3") (pin "L15") (pinfunction "GPIOR_187_PLLIN1_L15") (pintype "bidirectional"))
    )
    (net (code "129") (name "/D17_B_FromBUS") (class "Default")
      (node (ref "Lassye3") (pin "G10") (pinfunction "GPIOT_TXN26_G10") (pintype "bidirectional"))
    )
    (net (code "130") (name "/D17_B_ToBUS") (class "Default")
      (node (ref "Lassye3") (pin "M1") (pinfunction "GPIOL_65_CTRL3_M1") (pintype "bidirectional"))
    )
    (net (code "131") (name "/D18_A_FromBUS") (class "Default")
      (node (ref "Lassye3") (pin "G11") (pinfunction "GPIOT_RXP03_G11") (pintype "bidirectional"))
    )
    (net (code "132") (name "/D18_A_ToBUS") (class "Default")
      (node (ref "Lassye3") (pin "M3") (pinfunction "GPIOL_67_CLK1_M3") (pintype "bidirectional"))
    )
    (net (code "133") (name "/D18_B_FromBUS") (class "Default")
      (node (ref "Lassye3") (pin "G12") (pinfunction "GPIOT_RXN08_EXTFB0_G12") (pintype "bidirectional"))
    )
    (net (code "134") (name "/D18_B_ToBUS") (class "Default")
      (node (ref "Lassye3") (pin "M4") (pinfunction "GPIOL_64_CTRL2_M4") (pintype "bidirectional"))
    )
    (net (code "135") (name "/D19_A_FromBUS") (class "Default")
      (node (ref "Lassye3") (pin "G13") (pinfunction "GPIOT_RXN12_G13") (pintype "bidirectional"))
    )
    (net (code "136") (name "/D19_A_ToBUS") (class "Default")
      (node (ref "Lassye3") (pin "M7") (pinfunction "GPIOL_58_M7") (pintype "bidirectional"))
    )
    (net (code "137") (name "/D19_B_FromBUS") (class "Default")
      (node (ref "Lassye3") (pin "G14") (pinfunction "GPIOT_RXP16_G14") (pintype "bidirectional"))
    )
    (net (code "138") (name "/D19_B_ToBUS") (class "Default")
      (node (ref "Lassye3") (pin "M15") (pinfunction "GPIOR_186_PLLIN0_M15") (pintype "bidirectional"))
    )
    (net (code "139") (name "/D20_A_FromBUS") (class "Default")
      (node (ref "Lassye3") (pin "H1") (pinfunction "GPIOL_133_H1") (pintype "bidirectional"))
    )
    (net (code "140") (name "/D20_A_ToBUS") (class "Default")
      (node (ref "Lassye3") (pin "N1") (pinfunction "GPIOL_62_CTRL0_N1") (pintype "bidirectional"))
    )
    (net (code "141") (name "/D20_B_FromBUS") (class "Default")
      (node (ref "Lassye3") (pin "H3") (pinfunction "GPIOL_131_H3") (pintype "bidirectional"))
    )
    (net (code "142") (name "/D20_B_ToBUS") (class "Default")
      (node (ref "Lassye3") (pin "N2") (pinfunction "GPIOL_63_CTRL1_N2") (pintype "bidirectional"))
    )
    (net (code "143") (name "/D21_A_FromBUS") (class "Default")
      (node (ref "Lassye3") (pin "H4") (pinfunction "GPIOL_121_H4") (pintype "bidirectional"))
    )
    (net (code "144") (name "/D21_A_ToBUS") (class "Default")
      (node (ref "Lassye3") (pin "N4") (pinfunction "GPIOL_56_N4") (pintype "bidirectional"))
    )
    (net (code "145") (name "/D21_B_FromBUS") (class "Default")
      (node (ref "Lassye3") (pin "H6") (pinfunction "GPIOL_123_H6") (pintype "bidirectional"))
    )
    (net (code "146") (name "/D21_B_ToBUS") (class "Default")
      (node (ref "Lassye3") (pin "N5") (pinfunction "GPIOL_53_N5") (pintype "bidirectional"))
    )
    (net (code "147") (name "/D22_A_FromBUS") (class "Default")
      (node (ref "Lassye3") (pin "H7") (pinfunction "GPIOT_TXN15_H7") (pintype "bidirectional"))
    )
    (net (code "148") (name "/D22_A_ToBUS") (class "Default")
      (node (ref "Lassye3") (pin "N7") (pinfunction "GPIOL_40_N7") (pintype "bidirectional"))
    )
    (net (code "149") (name "/D22_B_FromBUS") (class "Default")
      (node (ref "Lassye3") (pin "H8") (pinfunction "GPIOT_TXP20_H8") (pintype "bidirectional"))
    )
    (net (code "150") (name "/D22_B_ToBUS") (class "Default")
      (node (ref "Lassye3") (pin "P5") (pinfunction "GPIOL_47_P5") (pintype "bidirectional"))
    )
    (net (code "151") (name "/D23_A_FromBUS") (class "Default")
      (node (ref "Lassye3") (pin "H9") (pinfunction "GPIOT_TXN22_H9") (pintype "bidirectional"))
    )
    (net (code "152") (name "/D23_A_ToBUS") (class "Default")
      (node (ref "Lassye3") (pin "P6") (pinfunction "GPIOL_45_P6") (pintype "bidirectional"))
    )
    (net (code "153") (name "/D23_B_FromBUS") (class "Default")
      (node (ref "Lassye3") (pin "H11") (pinfunction "GPIOT_RXN03_H11") (pintype "bidirectional"))
    )
    (net (code "154") (name "/D23_B_ToBUS") (class "Default")
      (node (ref "Lassye3") (pin "P7") (pinfunction "GPIOL_24_CDI7_P7") (pintype "bidirectional"))
    )
    (net (code "155") (name "/DataID_0") (class "Default")
      (node (ref "Lassye3") (pin "B11") (pinfunction "GPIOT_RXN01_B11") (pintype "bidirectional"))
    )
    (net (code "156") (name "/DataID_1") (class "Default")
      (node (ref "Lassye3") (pin "B10") (pinfunction "GPIOT_TXN25_B10") (pintype "bidirectional"))
    )
    (net (code "157") (name "/HOLD") (class "Default")
      (node (ref "EROM") (pin "7") (pinfunction "IO3_7") (pintype "passive"))
      (node (ref "R_Hold") (pin "1") (pinfunction "1_1") (pintype "passive"))
    )
    (net (code "158") (name "/INT") (class "Default")
      (node (ref "Lassye3") (pin "B9") (pinfunction "GPIOT_TXN23_B9") (pintype "bidirectional"))
    )
    (net (code "159") (name "/INT_A") (class "Default")
      (node (ref "Lassye3") (pin "B8") (pinfunction "GPIOT_TXP18_B8") (pintype "bidirectional"))
    )
    (net (code "160") (name "/INT_BUS") (class "Default")
      (node (ref "Lassye3") (pin "P8") (pinfunction "GPIOL_22_CDI6_P8") (pintype "bidirectional"))
    )
    (net (code "161") (name "/LOCK") (class "Default")
      (node (ref "Lassye3") (pin "C12") (pinfunction "GPIOT_RXN04_C12") (pintype "bidirectional"))
    )
    (net (code "162") (name "/MAIN_RESET") (class "Default")
      (node (ref "Lassye3") (pin "R8") (pinfunction "GPIOL_16_CDI3_R8") (pintype "bidirectional"))
    )
    (net (code "163") (name "/MISO") (class "Default")
      (node (ref "Lassye3") (pin "A4") (pinfunction "GPIOT_TXP06_A4") (pintype "bidirectional"))
    )
    (net (code "164") (name "/MOSI") (class "Default")
      (node (ref "Lassye3") (pin "A2") (pinfunction "GPIOT_TXP05_A2") (pintype "bidirectional"))
    )
    (net (code "165") (name "/MSync") (class "Default")
      (node (ref "Lassye3") (pin "A9") (pinfunction "GPIOT_TXP23_A9") (pintype "bidirectional"))
    )
    (net (code "166") (name "/M_IO") (class "Default")
      (node (ref "Lassye3") (pin "A11") (pinfunction "GPIOT_RXP01_A11") (pintype "bidirectional"))
    )
    (net (code "167") (name "/RAM_CLK") (class "Default")
      (node (ref "Lassye3") (pin "AA6") (pinfunction "GPIOB_TXN14_CDI16_AA6") (pintype "bidirectional"))
    )
    (net (code "168") (name "/RASn") (class "Default")
      (node (ref "Lassye3") (pin "AA7") (pinfunction "GPIOB_TXN16_CDI12_AA7") (pintype "bidirectional"))
    )
    (net (code "169") (name "/RESET_N") (class "Default")
      (node (ref "Lassye3") (pin "V4") (pinfunction "CRESET_N_V4") (pintype "input"))
    )
    (net (code "170") (name "/ROM_CSn") (class "Default")
      (node (ref "Lassye3") (pin "A21") (pinfunction "GPIOR_176_CLK13_A21") (pintype "bidirectional"))
    )
    (net (code "171") (name "/RTC_CLOCK") (class "Default")
      (node (ref "Lassye3") (pin "R12") (pinfunction "GPIOB_RXP09_CLKP0_R12") (pintype "bidirectional"))
    )
    (net (code "172") (name "/RTC_CSn") (class "Default")
      (node (ref "Lassye3") (pin "B21") (pinfunction "GPIOR_177_CLK12_B21") (pintype "bidirectional"))
    )
    (net (code "173") (name "/RTC_IRQ") (class "Default")
      (node (ref "Lassye3") (pin "A18") (pinfunction "GPIOR_167_PLLIN1_A18") (pintype "bidirectional"))
    )
    (net (code "174") (name "/RX_S1") (class "Default")
      (node (ref "Lassye3") (pin "B1") (pinfunction "GPIOT_TXN04_B1") (pintype "bidirectional"))
    )
    (net (code "175") (name "/RX_S2") (class "Default")
      (node (ref "Lassye3") (pin "C1") (pinfunction "GPIOT_TXP04_C1") (pintype "bidirectional"))
    )
    (net (code "176") (name "/R_W") (class "Default")
      (node (ref "Lassye3") (pin "A8") (pinfunction "GPIOT_TXN18_A8") (pintype "bidirectional"))
    )
    (net (code "177") (name "/R_W_Internal") (class "Default")
      (node (ref "Lassye3") (pin "D1") (pinfunction "GPIOT_TXP01_D1") (pintype "bidirectional"))
    )
    (net (code "178") (name "/Reset") (class "Default")
      (node (ref "Lassye3") (pin "A12") (pinfunction "GPIOT_RXP11_A12") (pintype "bidirectional"))
    )
    (net (code "179") (name "/SCLK") (class "Default")
      (node (ref "Lassye3") (pin "A3") (pinfunction "GPIOT_TXN06_A3") (pintype "bidirectional"))
    )
    (net (code "180") (name "/SDRAM_0") (class "Default")
      (node (ref "Lassye3") (pin "AB11") (pinfunction "GPIOB_RXP00_AB11") (pintype "bidirectional"))
    )
    (net (code "181") (name "/SDRAM_1") (class "Default")
      (node (ref "Lassye3") (pin "AB12") (pinfunction "GPIOB_RXN05_AB12") (pintype "bidirectional"))
    )
    (net (code "182") (name "/SDRAM_2") (class "Default")
      (node (ref "Lassye3") (pin "AB13") (pinfunction "GPIOB_RXP10_AB13") (pintype "bidirectional"))
    )
    (net (code "183") (name "/SDRAM_3") (class "Default")
      (node (ref "Lassye3") (pin "AB14") (pinfunction "GPIOB_RXN14_AB14") (pintype "bidirectional"))
    )
    (net (code "184") (name "/SDRAM_4") (class "Default")
      (node (ref "Lassye3") (pin "T13") (pinfunction "GPIOB_RXP12_T13") (pintype "bidirectional"))
    )
    (net (code "185") (name "/SDRAM_5") (class "Default")
      (node (ref "Lassye3") (pin "T14") (pinfunction "GPIOB_RXP18_EXTFB1_T14") (pintype "bidirectional"))
    )
    (net (code "186") (name "/SDRAM_6") (class "Default")
      (node (ref "Lassye3") (pin "AB17") (pinfunction "GPIOB_RXN28_EXTFB2_AB17") (pintype "bidirectional"))
    )
    (net (code "187") (name "/SDRAM_7") (class "Default")
      (node (ref "Lassye3") (pin "Y1") (pinfunction "GPIOB_TXN05_CDI26_Y1") (pintype "bidirectional"))
    )
    (net (code "188") (name "/SDRAM_8") (class "Default")
      (node (ref "Lassye3") (pin "Y6") (pinfunction "GPIOB_TXP13_CDI19_Y6") (pintype "bidirectional"))
    )
    (net (code "189") (name "/SDRAM_9") (class "Default")
      (node (ref "Lassye3") (pin "Y7") (pinfunction "GPIOB_TXN13_CDI18_Y7") (pintype "bidirectional"))
    )
    (net (code "190") (name "/SDRAM_10") (class "Default")
      (node (ref "Lassye3") (pin "Y13") (pinfunction "GPIOB_RXN16_Y13") (pintype "bidirectional"))
    )
    (net (code "191") (name "/SDRAM_11") (class "Default")
      (node (ref "Lassye3") (pin "Y14") (pinfunction "GPIOB_RXP16_Y14") (pintype "bidirectional"))
    )
    (net (code "192") (name "/SDRAM_12") (class "Default")
      (node (ref "Lassye3") (pin "W2") (pinfunction "GPIOB_TXP04_CDI29_W2") (pintype "bidirectional"))
    )
    (net (code "193") (name "/SDRAM_13") (class "Default")
      (node (ref "Lassye3") (pin "W3") (pinfunction "GPIOB_TXN04_CDI28_W3") (pintype "bidirectional"))
    )
    (net (code "194") (name "/SDRAM_14") (class "Default")
      (node (ref "Lassye3") (pin "W4") (pinfunction "GPIOB_TXN03_CDI30_W4") (pintype "bidirectional"))
    )
    (net (code "195") (name "/SDRAM_15") (class "Default")
      (node (ref "Lassye3") (pin "W8") (pinfunction "GPIOB_TXP17_CDI11_W8") (pintype "bidirectional"))
    )
    (net (code "196") (name "/SDRAM_16") (class "Default")
      (node (ref "Lassye3") (pin "W9") (pinfunction "GPIOB_TXN19_W9") (pintype "bidirectional"))
    )
    (net (code "197") (name "/SDRAM_17") (class "Default")
      (node (ref "Lassye3") (pin "W10") (pinfunction "GPIOB_TXP25_W10") (pintype "bidirectional"))
    )
    (net (code "198") (name "/SDRAM_18") (class "Default")
      (node (ref "Lassye3") (pin "W11") (pinfunction "GPIOB_RXP03_W11") (pintype "bidirectional"))
    )
    (net (code "199") (name "/SDRAM_19") (class "Default")
      (node (ref "Lassye3") (pin "W12") (pinfunction "GPIOB_RXN08_EXTFB0_W12") (pintype "bidirectional"))
    )
    (net (code "200") (name "/SDRAM_20") (class "Default")
      (node (ref "Lassye3") (pin "W14") (pinfunction "GPIOB_RXN19_CLKN1_W14") (pintype "bidirectional"))
    )
    (net (code "201") (name "/SDRAM_21") (class "Default")
      (node (ref "Lassye3") (pin "P1") (pinfunction "GPIOL_52_P1") (pintype "bidirectional"))
    )
    (net (code "202") (name "/SDRAM_22") (class "Default")
      (node (ref "Lassye3") (pin "P2") (pinfunction "GPIOL_50_P2") (pintype "bidirectional"))
    )
    (net (code "203") (name "/SDRAM_23") (class "Default")
      (node (ref "Lassye3") (pin "P3") (pinfunction "GPIOL_51_P3") (pintype "bidirectional"))
    )
    (net (code "204") (name "/SDRAM_24") (class "Default")
      (node (ref "Lassye3") (pin "V7") (pinfunction "GPIOB_TXP15_CDI15_V7") (pintype "bidirectional"))
    )
    (net (code "205") (name "/SDRAM_25") (class "Default")
      (node (ref "Lassye3") (pin "V8") (pinfunction "GPIOB_TXN17_CDI10_V8") (pintype "bidirectional"))
    )
    (net (code "206") (name "/SDRAM_26") (class "Default")
      (node (ref "Lassye3") (pin "V9") (pinfunction "GPIOB_TXP19_V9") (pintype "bidirectional"))
    )
    (net (code "207") (name "/SDRAM_27") (class "Default")
      (node (ref "Lassye3") (pin "V10") (pinfunction "GPIOB_TXN25_V10") (pintype "bidirectional"))
    )
    (net (code "208") (name "/SDRAM_28") (class "Default")
      (node (ref "Lassye3") (pin "V11") (pinfunction "GPIOB_RXN03_V11") (pintype "bidirectional"))
    )
    (net (code "209") (name "/SDRAM_29") (class "Default")
      (node (ref "Lassye3") (pin "V12") (pinfunction "GPIOB_RXP08_EXTFB0_V12") (pintype "bidirectional"))
    )
    (net (code "210") (name "/SDRAM_30") (class "Default")
      (node (ref "Lassye3") (pin "V14") (pinfunction "GPIOB_RXP19_CLKP1_V14") (pintype "bidirectional"))
    )
    (net (code "211") (name "/SDRAM_31") (class "Default")
      (node (ref "Lassye3") (pin "P4") (pinfunction "GPIOL_36_P4") (pintype "bidirectional"))
    )
    (net (code "212") (name "/SDRAM_32") (class "Default")
      (node (ref "Lassye3") (pin "U7") (pinfunction "GPIOB_TXN15_CDI14_U7") (pintype "bidirectional"))
    )
    (net (code "213") (name "/SDRAM_33") (class "Default")
      (node (ref "Lassye3") (pin "U8") (pinfunction "GPIOB_TXN18_CDI8_U8") (pintype "bidirectional"))
    )
    (net (code "214") (name "/SDRAM_34") (class "Default")
      (node (ref "Lassye3") (pin "U9") (pinfunction "GPIOB_TXP23_U9") (pintype "bidirectional"))
    )
    (net (code "215") (name "/SDRAM_35") (class "Default")
      (node (ref "Lassye3") (pin "U10") (pinfunction "GPIOB_TXN23_U10") (pintype "bidirectional"))
    )
    (net (code "216") (name "/SDRAM_36") (class "Default")
      (node (ref "Lassye3") (pin "U11") (pinfunction "GPIOB_RXP06_U11") (pintype "bidirectional"))
    )
    (net (code "217") (name "/SDRAM_37") (class "Default")
      (node (ref "Lassye3") (pin "U12") (pinfunction "GPIOB_RXN06_U12") (pintype "bidirectional"))
    )
    (net (code "218") (name "/SDRAM_38") (class "Default")
      (node (ref "Lassye3") (pin "U13") (pinfunction "GPIOB_RXN12_U13") (pintype "bidirectional"))
    )
    (net (code "219") (name "/SDRAM_39") (class "Default")
      (node (ref "Lassye3") (pin "U14") (pinfunction "GPIOB_RXN18_EXTFB1_U14") (pintype "bidirectional"))
    )
    (net (code "220") (name "/SDRAM_40") (class "Default")
      (node (ref "Lassye3") (pin "T6") (pinfunction "GPIOL_14_CDI2_T6") (pintype "bidirectional"))
    )
    (net (code "221") (name "/SDRAM_41") (class "Default")
      (node (ref "Lassye3") (pin "T8") (pinfunction "GPIOB_TXP18_CDI9_T8") (pintype "bidirectional"))
    )
    (net (code "222") (name "/SDRAM_42") (class "Default")
      (node (ref "Lassye3") (pin "T10") (pinfunction "GPIOB_RXP01_T10") (pintype "bidirectional"))
    )
    (net (code "223") (name "/SDRAM_43") (class "Default")
      (node (ref "Lassye3") (pin "R1") (pinfunction "GPIOL_49_R1") (pintype "bidirectional"))
    )
    (net (code "224") (name "/SDRAM_44") (class "Default")
      (node (ref "Lassye3") (pin "R2") (pinfunction "GPIOL_15_PLLIN0_R2") (pintype "bidirectional"))
    )
    (net (code "225") (name "/SDRAM_45") (class "Default")
      (node (ref "Lassye3") (pin "R3") (pinfunction "GPIOL_17_EXTFB0_R3") (pintype "bidirectional"))
    )
    (net (code "226") (name "/SDRAM_46") (class "Default")
      (node (ref "Lassye3") (pin "R6") (pinfunction "GPIOL_20_CDI5_R6") (pintype "bidirectional"))
    )
    (net (code "227") (name "/SDRAM_47") (class "Default")
      (node (ref "Lassye3") (pin "R7") (pinfunction "GPIOL_18_CDI4_R7") (pintype "bidirectional"))
    )
    (net (code "228") (name "/SDRAM_A0") (class "Default")
      (node (ref "Lassye3") (pin "AA13") (pinfunction "GPIOB_RXN10_AA13") (pintype "bidirectional"))
    )
    (net (code "229") (name "/SDRAM_A1") (class "Default")
      (node (ref "Lassye3") (pin "AA1") (pinfunction "GPIOB_TXP05_CDI27_AA1") (pintype "bidirectional"))
    )
    (net (code "230") (name "/SDRAM_A2") (class "Default")
      (node (ref "Lassye3") (pin "AA2") (pinfunction "GPIOB_TXN06_CDI24_AA2") (pintype "bidirectional"))
    )
    (net (code "231") (name "/SDRAM_A3") (class "Default")
      (node (ref "Lassye3") (pin "AB2") (pinfunction "GPIOB_TXP06_CDI25_AB2") (pintype "bidirectional"))
    )
    (net (code "232") (name "/SDRAM_A4") (class "Default")
      (node (ref "Lassye3") (pin "AB3") (pinfunction "GPIOB_TXP07_CDI23_AB3") (pintype "bidirectional"))
    )
    (net (code "233") (name "/SDRAM_A5") (class "Default")
      (node (ref "Lassye3") (pin "AB4") (pinfunction "GPIOB_TXN07_CDI22_AB4") (pintype "bidirectional"))
    )
    (net (code "234") (name "/SDRAM_A6") (class "Default")
      (node (ref "Lassye3") (pin "AB5") (pinfunction "GPIOB_TXN08_CDI20_AB5") (pintype "bidirectional"))
    )
    (net (code "235") (name "/SDRAM_A7") (class "Default")
      (node (ref "Lassye3") (pin "AB6") (pinfunction "GPIOB_TXP14_CDI17_AB6") (pintype "bidirectional"))
    )
    (net (code "236") (name "/SDRAM_A8") (class "Default")
      (node (ref "Lassye3") (pin "AB7") (pinfunction "GPIOB_TXP16_CDI13_AB7") (pintype "bidirectional"))
    )
    (net (code "237") (name "/SDRAM_A9") (class "Default")
      (node (ref "Lassye3") (pin "AB8") (pinfunction "GPIOB_TXP22_AB8") (pintype "bidirectional"))
    )
    (net (code "238") (name "/SDRAM_A10") (class "Default")
      (node (ref "Lassye3") (pin "AB9") (pinfunction "GPIOB_TXP24_AB9") (pintype "bidirectional"))
    )
    (net (code "239") (name "/SDRAM_A11") (class "Default")
      (node (ref "Lassye3") (pin "AB10") (pinfunction "GPIOB_TXP26_AB10") (pintype "bidirectional"))
    )
    (net (code "240") (name "/SDRAM_A12") (class "Default")
      (node (ref "Lassye3") (pin "R10") (pinfunction "GPIOB_RXN01_R10") (pintype "bidirectional"))
    )
    (net (code "243") (name "/SD_CSn") (class "Default")
      (node (ref "Lassye3") (pin "E1") (pinfunction "GPIOT_TXN01_E1") (pintype "bidirectional"))
    )
    (net (code "244") (name "/SPI_CLK") (class "Default")
      (node (ref "EROM") (pin "6") (pinfunction "CLK_6") (pintype "passive"))
      (node (ref "Lassye3") (pin "W1") (pinfunction "GPIOL_01_CCK_W1") (pintype "bidirectional"))
    )
    (net (code "245") (name "/SPI_MISO") (class "Default")
      (node (ref "EROM") (pin "2") (pinfunction "DO_(IO1)_2") (pintype "passive"))
      (node (ref "Lassye3") (pin "V1") (pinfunction "GPIOL_09_CDI1_V1") (pintype "bidirectional"))
      (node (ref "R_MISO") (pin "1") (pinfunction "1_1") (pintype "passive"))
    )
    (net (code "246") (name "/SPI_MOSI") (class "Default")
      (node (ref "EROM") (pin "5") (pinfunction "DI_(IO0)_5") (pintype "passive"))
      (node (ref "Lassye3") (pin "V2") (pinfunction "GPIOL_08_CDI0_V2") (pintype "bidirectional"))
      (node (ref "R_MOSI") (pin "1") (pinfunction "1_1") (pintype "passive"))
    )
    (net (code "247") (name "/SPI_SS") (class "Default")
      (node (ref "EROM") (pin "1") (pinfunction "/CS_1") (pintype "passive"))
      (node (ref "Lassye3") (pin "V3") (pinfunction "GPIOL_00_SS_N_V3") (pintype "bidirectional"))
      (node (ref "R_CS") (pin "1") (pinfunction "1_1") (pintype "passive"))
    )
    (net (code "248") (name "/SSync") (class "Default")
      (node (ref "Lassye3") (pin "A10") (pinfunction "GPIOT_TXP25_A10") (pintype "bidirectional"))
    )
    (net (code "249") (name "/TCK") (class "Default")
      (node (ref "CFG") (pin "2") (pinfunction "2_2") (pintype "passive"))
      (node (ref "Lassye3") (pin "T1") (pinfunction "TCK_T1") (pintype "input"))
    )
    (net (code "250") (name "/TDI") (class "Default")
      (node (ref "CFG") (pin "5") (pinfunction "5_5") (pintype "passive"))
      (node (ref "Lassye3") (pin "U2") (pinfunction "TDI_U2") (pintype "input"))
    )
    (net (code "251") (name "/TDO") (class "Default")
      (node (ref "CFG") (pin "3") (pinfunction "3_3") (pintype "passive"))
      (node (ref "Lassye3") (pin "T3") (pinfunction "TDO_T3") (pintype "output"))
    )
    (net (code "252") (name "/TMS") (class "Default")
      (node (ref "CFG") (pin "4") (pinfunction "4_4") (pintype "passive"))
      (node (ref "Lassye3") (pin "U1") (pinfunction "TMS_U1") (pintype "input"))
    )
    (net (code "253") (name "/TX_S1") (class "Default")
      (node (ref "Lassye3") (pin "B2") (pinfunction "GPIOT_TXN05_B2") (pintype "bidirectional"))
    )
    (net (code "254") (name "/TX_S2") (class "Default")
      (node (ref "Lassye3") (pin "C2") (pinfunction "GPIOT_TXN02_C2") (pintype "bidirectional"))
    )
    (net (code "255") (name "/Test_N") (class "Default")
      (node (ref "Lassye3") (pin "F1") (pinfunction "GPIOL_151_TEST_N_F1") (pintype "bidirectional"))
      (node (ref "Rk") (pin "4") (pinfunction "4_4") (pintype "passive"))
    )
    (net (code "256") (name "/VCCA_PLL") (class "Default")
      (node (ref "Lassye3") (pin "D17") (pinfunction "VCCA_TR_D17") (pintype "power_in"))
      (node (ref "Lassye3") (pin "D5") (pinfunction "VCCA_TL_D5") (pintype "power_in"))
      (node (ref "Lassye3") (pin "E17") (pinfunction "VCCA_TR_E17") (pintype "power_in"))
      (node (ref "Lassye3") (pin "N15") (pinfunction "VCCA_BR_N15") (pintype "power_in"))
      (node (ref "Lassye3") (pin "P15") (pinfunction "VCCA_BR_P15") (pintype "power_in"))
      (node (ref "Lassye3") (pin "W5") (pinfunction "VCCA_BL_W5") (pintype "power_in"))
    )
    (net (code "257") (name "/VCC_1V2") (class "Default")
      (node (ref "C_VCC0") (pin "2") (pinfunction "2_2") (pintype "passive"))
      (node (ref "C_VCC1") (pin "2") (pinfunction "2_2") (pintype "passive"))
      (node (ref "C_VCC2") (pin "2") (pinfunction "2_2") (pintype "passive"))
      (node (ref "C_VCC3") (pin "2") (pinfunction "2_2") (pintype "passive"))
      (node (ref "C_VCC4") (pin "2") (pinfunction "2_2") (pintype "passive"))
      (node (ref "C_VCC5") (pin "2") (pinfunction "2_2") (pintype "passive"))
      (node (ref "C_VCC6") (pin "2") (pinfunction "2_2") (pintype "passive"))
      (node (ref "C_VCC7") (pin "2") (pinfunction "2_2") (pintype "passive"))
      (node (ref "C_Vcc8") (pin "2") (pinfunction "2_2") (pintype "passive"))
      (node (ref "Lassye3") (pin "H10") (pinfunction "VCC_H10") (pintype "power_in"))
      (node (ref "Lassye3") (pin "J11") (pinfunction "VCC_J11") (pintype "power_in"))
      (node (ref "Lassye3") (pin "J13") (pinfunction "VCC_J13") (pintype "power_in"))
      (node (ref "Lassye3") (pin "J15") (pinfunction "VCC_J15") (pintype "power_in"))
      (node (ref "Lassye3") (pin "J9") (pinfunction "VCC_J9") (pintype "power_in"))
      (node (ref "Lassye3") (pin "K10") (pinfunction "VCC_K10") (pintype "power_in"))
      (node (ref "Lassye3") (pin "K12") (pinfunction "VCC_K12") (pintype "power_in"))
      (node (ref "Lassye3") (pin "K14") (pinfunction "VCC_K14") (pintype "power_in"))
      (node (ref "Lassye3") (pin "L11") (pinfunction "VCC_L11") (pintype "power_in"))
      (node (ref "Lassye3") (pin "L13") (pinfunction "VCC_L13") (pintype "power_in"))
      (node (ref "Lassye3") (pin "L9") (pinfunction "VCC_L9") (pintype "power_in"))
      (node (ref "Lassye3") (pin "M10") (pinfunction "VCC_M10") (pintype "power_in"))
      (node (ref "Lassye3") (pin "M12") (pinfunction "VCC_M12") (pintype "power_in"))
      (node (ref "Lassye3") (pin "M14") (pinfunction "VCC_M14") (pintype "power_in"))
      (node (ref "Lassye3") (pin "M8") (pinfunction "VCC_M8") (pintype "power_in"))
      (node (ref "Lassye3") (pin "N11") (pinfunction "VCC_N11") (pintype "power_in"))
      (node (ref "Lassye3") (pin "N13") (pinfunction "VCC_N13") (pintype "power_in"))
      (node (ref "Lassye3") (pin "N9") (pinfunction "VCC_N9") (pintype "power_in"))
      (node (ref "Lassye3") (pin "P10") (pinfunction "VCC_P10") (pintype "power_in"))
      (node (ref "Lassye3") (pin "P12") (pinfunction "VCC_P12") (pintype "power_in"))
      (node (ref "Lassye3") (pin "P14") (pinfunction "VCC_P14") (pintype "power_in"))
      (node (ref "Lassye3") (pin "R11") (pinfunction "VCC_R11") (pintype "power_in"))
    )
    (net (code "258") (name "/VDD") (class "Default")
      (node (ref "CFG") (pin "1") (pinfunction "1_1") (pintype "passive"))
      (node (ref "C_IO0") (pin "2") (pinfunction "2_2") (pintype "passive"))
      (node (ref "C_IO1") (pin "2") (pinfunction "2_2") (pintype "passive"))
      (node (ref "C_IO10") (pin "2") (pinfunction "2_2") (pintype "passive"))
      (node (ref "C_IO11") (pin "2") (pinfunction "2_2") (pintype "passive"))
      (node (ref "C_IO2") (pin "2") (pinfunction "2_2") (pintype "passive"))
      (node (ref "C_IO3") (pin "2") (pinfunction "2_2") (pintype "passive"))
      (node (ref "C_IO4") (pin "2") (pinfunction "2_2") (pintype "passive"))
      (node (ref "C_IO5") (pin "2") (pinfunction "2_2") (pintype "passive"))
      (node (ref "C_IO6") (pin "2") (pinfunction "2_2") (pintype "passive"))
      (node (ref "C_IO7") (pin "2") (pinfunction "2_2") (pintype "passive"))
      (node (ref "C_IO8") (pin "2") (pinfunction "2_2") (pintype "passive"))
      (node (ref "C_IO9") (pin "2") (pinfunction "2_2") (pintype "passive"))
      (node (ref "C_ROM") (pin "2") (pinfunction "2_2") (pintype "passive"))
      (node (ref "EROM") (pin "8") (pinfunction "VCC_8") (pintype "passive"))
      (node (ref "Lassye3") (pin "AA14") (pinfunction "VCCIO4B_AA14") (pintype "power_in"))
      (node (ref "Lassye3") (pin "AA4") (pinfunction "VCCIO4F_AA4") (pintype "power_in"))
      (node (ref "Lassye3") (pin "B18") (pinfunction "VCCIO3D_TR_BR_B18") (pintype "power_in"))
      (node (ref "Lassye3") (pin "B3") (pinfunction "VCCIO2A_B3") (pintype "power_in"))
      (node (ref "Lassye3") (pin "C14") (pinfunction "VCCIO2E_C14") (pintype "power_in"))
      (node (ref "Lassye3") (pin "C17") (pinfunction "VCCIO2F_C17") (pintype "power_in"))
      (node (ref "Lassye3") (pin "C20") (pinfunction "VCCIO3D_TR_BR_C20") (pintype "power_in"))
      (node (ref "Lassye3") (pin "C8") (pinfunction "VCCIO2B_C8") (pintype "power_in"))
      (node (ref "Lassye3") (pin "C9") (pinfunction "VCCIO2C_C9") (pintype "power_in"))
      (node (ref "Lassye3") (pin "D12") (pinfunction "VCCIO2D_D12") (pintype "power_in"))
      (node (ref "Lassye3") (pin "D3") (pinfunction "VCCIO2A_D3") (pintype "power_in"))
      (node (ref "Lassye3") (pin "D6") (pinfunction "VCCIO2B_D6") (pintype "power_in"))
      (node (ref "Lassye3") (pin "F11") (pinfunction "VCCIO2D_F11") (pintype "power_in"))
      (node (ref "Lassye3") (pin "F14") (pinfunction "VCCIO2E_F14") (pintype "power_in"))
      (node (ref "Lassye3") (pin "F2") (pinfunction "VCCIO1F_1G_F2") (pintype "power_in"))
      (node (ref "Lassye3") (pin "F3") (pinfunction "VCCIO1F_1G_F3") (pintype "power_in"))
      (node (ref "Lassye3") (pin "F9") (pinfunction "VCCIO2C_F9") (pintype "power_in"))
      (node (ref "Lassye3") (pin "G16") (pinfunction "VCCIO2F_G16") (pintype "power_in"))
      (node (ref "Lassye3") (pin "J6") (pinfunction "VCCIO1D_1E_J6") (pintype "power_in"))
      (node (ref "Lassye3") (pin "K3") (pinfunction "VCCIO1D_1E_K3") (pintype "power_in"))
      (node (ref "Lassye3") (pin "N3") (pinfunction "VCCIO1B_1C_N3") (pintype "power_in"))
      (node (ref "Lassye3") (pin "N6") (pinfunction "VCCIO1B_1C_N6") (pintype "power_in"))
      (node (ref "Lassye3") (pin "R5") (pinfunction "VCCIO1B_1C_R5") (pintype "power_in"))
      (node (ref "Lassye3") (pin "R9") (pinfunction "VCCIO4E_R9") (pintype "power_in"))
      (node (ref "Lassye3") (pin "T11") (pinfunction "VCCIO4C_T11") (pintype "power_in"))
      (node (ref "Lassye3") (pin "T9") (pinfunction "VCCIO4D_T9") (pintype "power_in"))
      (node (ref "Lassye3") (pin "U15") (pinfunction "VCCIO4A_U15") (pintype "power_in"))
      (node (ref "Lassye3") (pin "U3") (pinfunction "VCCIO1A_U3") (pintype "power_in"))
      (node (ref "Lassye3") (pin "V13") (pinfunction "VCCIO4B_V13") (pintype "power_in"))
      (node (ref "Lassye3") (pin "W7") (pinfunction "VCCIO4E_W7") (pintype "power_in"))
      (node (ref "Lassye3") (pin "Y12") (pinfunction "VCCIO4C_Y12") (pintype "power_in"))
      (node (ref "Lassye3") (pin "Y16") (pinfunction "VCCIO4A_Y16") (pintype "power_in"))
      (node (ref "Lassye3") (pin "Y3") (pinfunction "VCCIO4F_Y3") (pintype "power_in"))
      (node (ref "Lassye3") (pin "Y9") (pinfunction "VCCIO4D_Y9") (pintype "power_in"))
      (node (ref "R_CDONE") (pin "1") (pinfunction "1_1") (pintype "passive"))
      (node (ref "R_CS") (pin "2") (pinfunction "2_2") (pintype "passive"))
      (node (ref "R_CSI") (pin "2") (pinfunction "2_2") (pintype "passive"))
      (node (ref "R_Hold") (pin "2") (pinfunction "2_2") (pintype "passive"))
      (node (ref "R_MISO") (pin "2") (pinfunction "2_2") (pintype "passive"))
      (node (ref "R_MOSI") (pin "2") (pinfunction "2_2") (pintype "passive"))
      (node (ref "R_WP") (pin "2") (pinfunction "2_2") (pintype "passive"))
      (node (ref "Rk") (pin "5") (pinfunction "5_5") (pintype "passive"))
      (node (ref "Rk") (pin "6") (pinfunction "6_6") (pintype "passive"))
      (node (ref "Rk") (pin "7") (pinfunction "7_7") (pintype "passive"))
      (node (ref "Rk") (pin "8") (pinfunction "8_8") (pintype "passive"))
    )
    (net (code "259") (name "/WEn") (class "Default")
      (node (ref "Lassye3") (pin "AA9") (pinfunction "GPIOB_TXN24_AA9") (pintype "bidirectional"))
    )
    (net (code "260") (name "/Wait") (class "Default")
      (node (ref "Lassye3") (pin "A13") (pinfunction "GPIOT_RXN11_A13") (pintype "bidirectional"))
    )
    (net (code "261") (name "GND") (class "Default")
      (node (ref "CFG") (pin "6") (pinfunction "6_6") (pintype "passive"))
      (node (ref "C_IO0") (pin "1") (pinfunction "1_1") (pintype "passive"))
      (node (ref "C_IO1") (pin "1") (pinfunction "1_1") (pintype "passive"))
      (node (ref "C_IO10") (pin "1") (pinfunction "1_1") (pintype "passive"))
      (node (ref "C_IO11") (pin "1") (pinfunction "1_1") (pintype "passive"))
      (node (ref "C_IO2") (pin "1") (pinfunction "1_1") (pintype "passive"))
      (node (ref "C_IO3") (pin "1") (pinfunction "1_1") (pintype "passive"))
      (node (ref "C_IO4") (pin "1") (pinfunction "1_1") (pintype "passive"))
      (node (ref "C_IO5") (pin "1") (pinfunction "1_1") (pintype "passive"))
      (node (ref "C_IO6") (pin "1") (pinfunction "1_1") (pintype "passive"))
      (node (ref "C_IO7") (pin "1") (pinfunction "1_1") (pintype "passive"))
      (node (ref "C_IO8") (pin "1") (pinfunction "1_1") (pintype "passive"))
      (node (ref "C_IO9") (pin "1") (pinfunction "1_1") (pintype "passive"))
      (node (ref "C_ROM") (pin "1") (pinfunction "1_1") (pintype "passive"))
      (node (ref "C_VCC0") (pin "1") (pinfunction "1_1") (pintype "passive"))
      (node (ref "C_VCC1") (pin "1") (pinfunction "1_1") (pintype "passive"))
      (node (ref "C_VCC2") (pin "1") (pinfunction "1_1") (pintype "passive"))
      (node (ref "C_VCC3") (pin "1") (pinfunction "1_1") (pintype "passive"))
      (node (ref "C_VCC4") (pin "1") (pinfunction "1_1") (pintype "passive"))
      (node (ref "C_VCC5") (pin "1") (pinfunction "1_1") (pintype "passive"))
      (node (ref "C_VCC6") (pin "1") (pinfunction "1_1") (pintype "passive"))
      (node (ref "C_VCC7") (pin "1") (pinfunction "1_1") (pintype "passive"))
      (node (ref "C_Vcc8") (pin "1") (pinfunction "1_1") (pintype "passive"))
      (node (ref "EROM") (pin "4") (pinfunction "GND_4") (pintype "passive"))
      (node (ref "Lassye3") (pin "A1") (pinfunction "GND_A1") (pintype "power_in"))
      (node (ref "Lassye3") (pin "A22") (pinfunction "GND_A22") (pintype "power_in"))
      (node (ref "Lassye3") (pin "AB1") (pinfunction "GND_AB1") (pintype "power_in"))
      (node (ref "Lassye3") (pin "AB22") (pinfunction "GND_AB22") (pintype "power_in"))
      (node (ref "Lassye3") (pin "B12") (pinfunction "GND_B12") (pintype "power_in"))
      (node (ref "Lassye3") (pin "B4") (pinfunction "GND_B4") (pintype "power_in"))
      (node (ref "Lassye3") (pin "D13") (pinfunction "GND_D13") (pintype "power_in"))
      (node (ref "Lassye3") (pin "D16") (pinfunction "GND_D16") (pintype "power_in"))
      (node (ref "Lassye3") (pin "D4") (pinfunction "GND_D4") (pintype "power_in"))
      (node (ref "Lassye3") (pin "D7") (pinfunction "GND_D7") (pintype "power_in"))
      (node (ref "Lassye3") (pin "E18") (pinfunction "GND_E18") (pintype "power_in"))
      (node (ref "Lassye3") (pin "E20") (pinfunction "GND_E20") (pintype "power_in"))
      (node (ref "Lassye3") (pin "F22") (pinfunction "GND_F22") (pintype "power_in"))
      (node (ref "Lassye3") (pin "H15") (pinfunction "GND_H15") (pintype "power_in"))
      (node (ref "Lassye3") (pin "H17") (pinfunction "GND_H17") (pintype "power_in"))
      (node (ref "Lassye3") (pin "H2") (pinfunction "GND_H2") (pintype "power_in"))
      (node (ref "Lassye3") (pin "H22") (pinfunction "GND_H22") (pintype "power_in"))
      (node (ref "Lassye3") (pin "H5") (pinfunction "GND_H5") (pintype "power_in"))
      (node (ref "Lassye3") (pin "J10") (pinfunction "GND_J10") (pintype "power_in"))
      (node (ref "Lassye3") (pin "J12") (pinfunction "GND_J12") (pintype "power_in"))
      (node (ref "Lassye3") (pin "J14") (pinfunction "GND_J14") (pintype "power_in"))
      (node (ref "Lassye3") (pin "J20") (pinfunction "GND_J20") (pintype "power_in"))
      (node (ref "Lassye3") (pin "K11") (pinfunction "GND_K11") (pintype "power_in"))
      (node (ref "Lassye3") (pin "K13") (pinfunction "GND_K13") (pintype "power_in"))
      (node (ref "Lassye3") (pin "K16") (pinfunction "GND_K16") (pintype "power_in"))
      (node (ref "Lassye3") (pin "K17") (pinfunction "DDR_VREF_K17") (pintype "bidirectional"))
      (node (ref "Lassye3") (pin "K18") (pinfunction "GND_K18") (pintype "power_in"))
      (node (ref "Lassye3") (pin "K9") (pinfunction "GND_K9") (pintype "power_in"))
      (node (ref "Lassye3") (pin "L10") (pinfunction "GND_L10") (pintype "power_in"))
      (node (ref "Lassye3") (pin "L12") (pinfunction "GND_L12") (pintype "power_in"))
      (node (ref "Lassye3") (pin "L14") (pinfunction "GND_L14") (pintype "power_in"))
      (node (ref "Lassye3") (pin "L8") (pinfunction "GND_L8") (pintype "power_in"))
      (node (ref "Lassye3") (pin "M11") (pinfunction "GND_M11") (pintype "power_in"))
      (node (ref "Lassye3") (pin "M13") (pinfunction "GND_M13") (pintype "power_in"))
      (node (ref "Lassye3") (pin "M2") (pinfunction "GND_M2") (pintype "power_in"))
      (node (ref "Lassye3") (pin "M5") (pinfunction "GND_M5") (pintype "power_in"))
      (node (ref "Lassye3") (pin "M9") (pinfunction "GND_M9") (pintype "power_in"))
      (node (ref "Lassye3") (pin "N10") (pinfunction "GND_N10") (pintype "power_in"))
      (node (ref "Lassye3") (pin "N12") (pinfunction "GND_N12") (pintype "power_in"))
      (node (ref "Lassye3") (pin "N14") (pinfunction "GND_N14") (pintype "power_in"))
      (node (ref "Lassye3") (pin "N16") (pinfunction "GND_N16") (pintype "power_in"))
      (node (ref "Lassye3") (pin "N18") (pinfunction "GND_N18") (pintype "power_in"))
      (node (ref "Lassye3") (pin "N20") (pinfunction "GND_N20") (pintype "power_in"))
      (node (ref "Lassye3") (pin "N22") (pinfunction "GND_N22") (pintype "power_in"))
      (node (ref "Lassye3") (pin "N8") (pinfunction "GND_N8") (pintype "power_in"))
      (node (ref "Lassye3") (pin "P11") (pinfunction "GND_P11") (pintype "power_in"))
      (node (ref "Lassye3") (pin "P13") (pinfunction "GND_P13") (pintype "power_in"))
      (node (ref "Lassye3") (pin "P9") (pinfunction "GND_P9") (pintype "power_in"))
      (node (ref "Lassye3") (pin "T16") (pinfunction "GND_T16") (pintype "power_in"))
      (node (ref "Lassye3") (pin "T18") (pinfunction "GND_T18") (pintype "power_in"))
      (node (ref "Lassye3") (pin "T2") (pinfunction "GND_T2") (pintype "power_in"))
      (node (ref "Lassye3") (pin "T5") (pinfunction "GND_T5") (pintype "power_in"))
      (node (ref "Lassye3") (pin "T7") (pinfunction "GND_T7") (pintype "power_in"))
      (node (ref "Lassye3") (pin "U20") (pinfunction "GND_U20") (pintype "power_in"))
      (node (ref "Lassye3") (pin "U22") (pinfunction "GND_U22") (pintype "power_in"))
      (node (ref "Lassye3") (pin "W13") (pinfunction "GND_W13") (pintype "power_in"))
      (node (ref "Lassye3") (pin "W18") (pinfunction "GND_W18") (pintype "power_in"))
      (node (ref "Lassye3") (pin "Y11") (pinfunction "GND_Y11") (pintype "power_in"))
      (node (ref "Lassye3") (pin "Y15") (pinfunction "GND_Y15") (pintype "power_in"))
      (node (ref "Lassye3") (pin "Y2") (pinfunction "GND_Y2") (pintype "power_in"))
      (node (ref "Lassye3") (pin "Y20") (pinfunction "GND_Y20") (pintype "power_in"))
      (node (ref "Lassye3") (pin "Y5") (pinfunction "GND_Y5") (pintype "power_in"))
      (node (ref "Lassye3") (pin "Y8") (pinfunction "GND_Y8") (pintype "power_in"))
    )
    (net (code "262") (name "INTn") (class "Default")
      (node (ref "Lassye3") (pin "K1") (pinfunction "GPIOL_87_K1") (pintype "bidirectional"))
    )
    (net (code "263") (name "Net-(EROM-IO2)") (class "Default")
      (node (ref "EROM") (pin "3") (pinfunction "IO2_3") (pintype "passive"))
      (node (ref "R_WP") (pin "1") (pinfunction "1_1") (pintype "passive"))
    )
    (net (code "264") (name "Net-(Lassye3C-GPIOL_04_CSI)") (class "Default")
      (node (ref "Lassye3") (pin "V6") (pinfunction "GPIOL_04_CSI_V6") (pintype "bidirectional"))
      (node (ref "R_CSI") (pin "1") (pinfunction "1_1") (pintype "passive"))
    )
    (net (code "265") (name "SCS") (class "Default")
      (node (ref "Lassye3") (pin "J1") (pinfunction "GPIOL_119_J1") (pintype "bidirectional"))
    )
    (net (code "266") (name "unconnected-(Lassye3A-DDR_A[0]-PadM18)") (class "Default")
      (node (ref "Lassye3") (pin "M18") (pinfunction "DDR_A[0]_M18") (pintype "output"))
    )
    (net (code "267") (name "unconnected-(Lassye3A-DDR_A[1]-PadL17)") (class "Default")
      (node (ref "Lassye3") (pin "L17") (pinfunction "DDR_A[1]_L17") (pintype "output"))
    )
    (net (code "268") (name "unconnected-(Lassye3A-DDR_A[2]-PadN17)") (class "Default")
      (node (ref "Lassye3") (pin "N17") (pinfunction "DDR_A[2]_N17") (pintype "output"))
    )
    (net (code "269") (name "unconnected-(Lassye3A-DDR_A[3]-PadP20)") (class "Default")
      (node (ref "Lassye3") (pin "P20") (pinfunction "DDR_A[3]_P20") (pintype "output"))
    )
    (net (code "270") (name "unconnected-(Lassye3A-DDR_A[4]-PadN19)") (class "Default")
      (node (ref "Lassye3") (pin "N19") (pinfunction "DDR_A[4]_N19") (pintype "output"))
    )
    (net (code "271") (name "unconnected-(Lassye3A-DDR_A[5]-PadT19)") (class "Default")
      (node (ref "Lassye3") (pin "T19") (pinfunction "DDR_A[5]_T19") (pintype "output"))
    )
    (net (code "272") (name "unconnected-(Lassye3A-DDR_A[6]-PadM20)") (class "Default")
      (node (ref "Lassye3") (pin "M20") (pinfunction "DDR_A[6]_M20") (pintype "output"))
    )
    (net (code "273") (name "unconnected-(Lassye3A-DDR_A[7]-PadP17)") (class "Default")
      (node (ref "Lassye3") (pin "P17") (pinfunction "DDR_A[7]_P17") (pintype "output"))
    )
    (net (code "274") (name "unconnected-(Lassye3A-DDR_A[8]-PadP19)") (class "Default")
      (node (ref "Lassye3") (pin "P19") (pinfunction "DDR_A[8]_P19") (pintype "output"))
    )
    (net (code "275") (name "unconnected-(Lassye3A-DDR_A[9]-PadR20)") (class "Default")
      (node (ref "Lassye3") (pin "R20") (pinfunction "DDR_A[9]_R20") (pintype "output"))
    )
    (net (code "276") (name "unconnected-(Lassye3A-DDR_A[10]-PadP22)") (class "Default")
      (node (ref "Lassye3") (pin "P22") (pinfunction "DDR_A[10]_P22") (pintype "output"))
    )
    (net (code "277") (name "unconnected-(Lassye3A-DDR_A[11]-PadR22)") (class "Default")
      (node (ref "Lassye3") (pin "R22") (pinfunction "DDR_A[11]_R22") (pintype "output+no_connect"))
    )
    (net (code "278") (name "unconnected-(Lassye3A-DDR_A[12]-PadT20)") (class "Default")
      (node (ref "Lassye3") (pin "T20") (pinfunction "DDR_A[12]_T20") (pintype "output"))
    )
    (net (code "279") (name "unconnected-(Lassye3A-DDR_A[13]-PadT21)") (class "Default")
      (node (ref "Lassye3") (pin "T21") (pinfunction "DDR_A[13]_T21") (pintype "output"))
    )
    (net (code "280") (name "unconnected-(Lassye3A-DDR_A[14]-PadR18)") (class "Default")
      (node (ref "Lassye3") (pin "R18") (pinfunction "DDR_A[14]_R18") (pintype "output"))
    )
    (net (code "281") (name "unconnected-(Lassye3A-DDR_A[15]-PadU17)") (class "Default")
      (node (ref "Lassye3") (pin "U17") (pinfunction "DDR_A[15]_U17") (pintype "output"))
    )
    (net (code "282") (name "unconnected-(Lassye3A-DDR_BA[0]-PadV16)") (class "Default")
      (node (ref "Lassye3") (pin "V16") (pinfunction "DDR_BA[0]_V16") (pintype "output"))
    )
    (net (code "283") (name "unconnected-(Lassye3A-DDR_BA[1]-PadT17)") (class "Default")
      (node (ref "Lassye3") (pin "T17") (pinfunction "DDR_BA[1]_T17") (pintype "output"))
    )
    (net (code "284") (name "unconnected-(Lassye3A-DDR_BA[2]-PadW16)") (class "Default")
      (node (ref "Lassye3") (pin "W16") (pinfunction "DDR_BA[2]_W16") (pintype "output"))
    )
    (net (code "285") (name "unconnected-(Lassye3A-DDR_CAS_N-PadM16)") (class "Default")
      (node (ref "Lassye3") (pin "M16") (pinfunction "DDR_CAS_N_M16") (pintype "output"))
    )
    (net (code "286") (name "unconnected-(Lassye3A-DDR_CK-PadN21)") (class "Default")
      (node (ref "Lassye3") (pin "N21") (pinfunction "DDR_CK_N21") (pintype "output"))
    )
    (net (code "287") (name "unconnected-(Lassye3A-DDR_CKE-PadL16)") (class "Default")
      (node (ref "Lassye3") (pin "L16") (pinfunction "DDR_CKE_L16") (pintype "output"))
    )
    (net (code "288") (name "unconnected-(Lassye3A-DDR_CK_N-PadP21)") (class "Default")
      (node (ref "Lassye3") (pin "P21") (pinfunction "DDR_CK_N_P21") (pintype "output"))
    )
    (net (code "289") (name "unconnected-(Lassye3A-DDR_CS_N-PadP16)") (class "Default")
      (node (ref "Lassye3") (pin "P16") (pinfunction "DDR_CS_N_P16") (pintype "output"))
    )
    (net (code "290") (name "unconnected-(Lassye3A-DDR_DM[0]-PadK19)") (class "Default")
      (node (ref "Lassye3") (pin "K19") (pinfunction "DDR_DM[0]_K19") (pintype "output"))
    )
    (net (code "291") (name "unconnected-(Lassye3A-DDR_DM[1]-PadG22)") (class "Default")
      (node (ref "Lassye3") (pin "G22") (pinfunction "DDR_DM[1]_G22") (pintype "output"))
    )
    (net (code "292") (name "unconnected-(Lassye3A-DDR_DM[2]-PadV20)") (class "Default")
      (node (ref "Lassye3") (pin "V20") (pinfunction "DDR_DM[2]_V20") (pintype "output"))
    )
    (net (code "293") (name "unconnected-(Lassye3A-DDR_DM[3]-PadY19)") (class "Default")
      (node (ref "Lassye3") (pin "Y19") (pinfunction "DDR_DM[3]_Y19") (pintype "output"))
    )
    (net (code "294") (name "unconnected-(Lassye3A-DDR_ODT-PadW17)") (class "Default")
      (node (ref "Lassye3") (pin "W17") (pinfunction "DDR_ODT_W17") (pintype "output"))
    )
    (net (code "295") (name "unconnected-(Lassye3A-DDR_RAS_N-PadR16)") (class "Default")
      (node (ref "Lassye3") (pin "R16") (pinfunction "DDR_RAS_N_R16") (pintype "output"))
    )
    (net (code "296") (name "unconnected-(Lassye3A-DDR_RST_N-PadY17)") (class "Default")
      (node (ref "Lassye3") (pin "Y17") (pinfunction "DDR_RST_N_Y17") (pintype "output"))
    )
    (net (code "297") (name "unconnected-(Lassye3A-DDR_WE_N-PadU16)") (class "Default")
      (node (ref "Lassye3") (pin "U16") (pinfunction "DDR_WE_N_U16") (pintype "output"))
    )
    (net (code "298") (name "unconnected-(Lassye3B-DDR_DQS[0]-PadL21)") (class "Default")
      (node (ref "Lassye3") (pin "L21") (pinfunction "DDR_DQS[0]_L21") (pintype "bidirectional"))
    )
    (net (code "299") (name "unconnected-(Lassye3B-DDR_DQS[1]-PadG20)") (class "Default")
      (node (ref "Lassye3") (pin "G20") (pinfunction "DDR_DQS[1]_G20") (pintype "bidirectional"))
    )
    (net (code "300") (name "unconnected-(Lassye3B-DDR_DQS[2]-PadV22)") (class "Default")
      (node (ref "Lassye3") (pin "V22") (pinfunction "DDR_DQS[2]_V22") (pintype "bidirectional"))
    )
    (net (code "301") (name "unconnected-(Lassye3B-DDR_DQS[3]-PadAB21)") (class "Default")
      (node (ref "Lassye3") (pin "AB21") (pinfunction "DDR_DQS[3]_AB21") (pintype "bidirectional"))
    )
    (net (code "302") (name "unconnected-(Lassye3B-DDR_DQS_N[0]-PadL22)") (class "Default")
      (node (ref "Lassye3") (pin "L22") (pinfunction "DDR_DQS_N[0]_L22") (pintype "bidirectional"))
    )
    (net (code "303") (name "unconnected-(Lassye3B-DDR_DQS_N[1]-PadG21)") (class "Default")
      (node (ref "Lassye3") (pin "G21") (pinfunction "DDR_DQS_N[1]_G21") (pintype "bidirectional"))
    )
    (net (code "304") (name "unconnected-(Lassye3B-DDR_DQS_N[2]-PadW22)") (class "Default")
      (node (ref "Lassye3") (pin "W22") (pinfunction "DDR_DQS_N[2]_W22") (pintype "bidirectional"))
    )
    (net (code "305") (name "unconnected-(Lassye3B-DDR_DQS_N[3]-PadAB20)") (class "Default")
      (node (ref "Lassye3") (pin "AB20") (pinfunction "DDR_DQS_N[3]_AB20") (pintype "bidirectional"))
    )
    (net (code "306") (name "unconnected-(Lassye3B-DDR_DQ[0]-PadK21)") (class "Default")
      (node (ref "Lassye3") (pin "K21") (pinfunction "DDR_DQ[0]_K21") (pintype "bidirectional"))
    )
    (net (code "307") (name "unconnected-(Lassye3B-DDR_DQ[1]-PadM22)") (class "Default")
      (node (ref "Lassye3") (pin "M22") (pinfunction "DDR_DQ[1]_M22") (pintype "bidirectional"))
    )
    (net (code "308") (name "unconnected-(Lassye3B-DDR_DQ[2]-PadK20)") (class "Default")
      (node (ref "Lassye3") (pin "K20") (pinfunction "DDR_DQ[2]_K20") (pintype "bidirectional"))
    )
    (net (code "309") (name "unconnected-(Lassye3B-DDR_DQ[3]-PadL20)") (class "Default")
      (node (ref "Lassye3") (pin "L20") (pinfunction "DDR_DQ[3]_L20") (pintype "bidirectional"))
    )
    (net (code "310") (name "unconnected-(Lassye3B-DDR_DQ[4]-PadL19)") (class "Default")
      (node (ref "Lassye3") (pin "L19") (pinfunction "DDR_DQ[4]_L19") (pintype "bidirectional"))
    )
    (net (code "311") (name "unconnected-(Lassye3B-DDR_DQ[5]-PadJ18)") (class "Default")
      (node (ref "Lassye3") (pin "J18") (pinfunction "DDR_DQ[5]_J18") (pintype "bidirectional"))
    )
    (net (code "312") (name "unconnected-(Lassye3B-DDR_DQ[6]-PadL18)") (class "Default")
      (node (ref "Lassye3") (pin "L18") (pinfunction "DDR_DQ[6]_L18") (pintype "bidirectional"))
    )
    (net (code "313") (name "unconnected-(Lassye3B-DDR_DQ[7]-PadH18)") (class "Default")
      (node (ref "Lassye3") (pin "H18") (pinfunction "DDR_DQ[7]_H18") (pintype "bidirectional"))
    )
    (net (code "314") (name "unconnected-(Lassye3B-DDR_DQ[8]-PadJ22)") (class "Default")
      (node (ref "Lassye3") (pin "J22") (pinfunction "DDR_DQ[8]_J22") (pintype "bidirectional"))
    )
    (net (code "315") (name "unconnected-(Lassye3B-DDR_DQ[9]-PadK22)") (class "Default")
      (node (ref "Lassye3") (pin "K22") (pinfunction "DDR_DQ[9]_K22") (pintype "bidirectional"))
    )
    (net (code "316") (name "unconnected-(Lassye3B-DDR_DQ[10]-PadH20)") (class "Default")
      (node (ref "Lassye3") (pin "H20") (pinfunction "DDR_DQ[10]_H20") (pintype "bidirectional"))
    )
    (net (code "317") (name "unconnected-(Lassye3B-DDR_DQ[11]-PadH19)") (class "Default")
      (node (ref "Lassye3") (pin "H19") (pinfunction "DDR_DQ[11]_H19") (pintype "bidirectional"))
    )
    (net (code "318") (name "unconnected-(Lassye3B-DDR_DQ[12]-PadG19)") (class "Default")
      (node (ref "Lassye3") (pin "G19") (pinfunction "DDR_DQ[12]_G19") (pintype "bidirectional"))
    )
    (net (code "319") (name "unconnected-(Lassye3B-DDR_DQ[13]-PadH21)") (class "Default")
      (node (ref "Lassye3") (pin "H21") (pinfunction "DDR_DQ[13]_H21") (pintype "bidirectional"))
    )
    (net (code "320") (name "unconnected-(Lassye3B-DDR_DQ[14]-PadF20)") (class "Default")
      (node (ref "Lassye3") (pin "F20") (pinfunction "DDR_DQ[14]_F20") (pintype "bidirectional"))
    )
    (net (code "321") (name "unconnected-(Lassye3B-DDR_DQ[15]-PadF18)") (class "Default")
      (node (ref "Lassye3") (pin "F18") (pinfunction "DDR_DQ[15]_F18") (pintype "bidirectional"))
    )
    (net (code "322") (name "unconnected-(Lassye3B-DDR_DQ[16]-PadU19)") (class "Default")
      (node (ref "Lassye3") (pin "U19") (pinfunction "DDR_DQ[16]_U19") (pintype "bidirectional"))
    )
    (net (code "323") (name "unconnected-(Lassye3B-DDR_DQ[17]-PadT22)") (class "Default")
      (node (ref "Lassye3") (pin "T22") (pinfunction "DDR_DQ[17]_T22") (pintype "bidirectional"))
    )
    (net (code "324") (name "unconnected-(Lassye3B-DDR_DQ[18]-PadW21)") (class "Default")
      (node (ref "Lassye3") (pin "W21") (pinfunction "DDR_DQ[18]_W21") (pintype "bidirectional"))
    )
    (net (code "325") (name "unconnected-(Lassye3B-DDR_DQ[19]-PadU21)") (class "Default")
      (node (ref "Lassye3") (pin "U21") (pinfunction "DDR_DQ[19]_U21") (pintype "bidirectional"))
    )
    (net (code "326") (name "unconnected-(Lassye3B-DDR_DQ[20]-PadU18)") (class "Default")
      (node (ref "Lassye3") (pin "U18") (pinfunction "DDR_DQ[20]_U18") (pintype "bidirectional"))
    )
    (net (code "327") (name "unconnected-(Lassye3B-DDR_DQ[21]-PadW20)") (class "Default")
      (node (ref "Lassye3") (pin "W20") (pinfunction "DDR_DQ[21]_W20") (pintype "bidirectional"))
    )
    (net (code "328") (name "unconnected-(Lassye3B-DDR_DQ[22]-PadW19)") (class "Default")
      (node (ref "Lassye3") (pin "W19") (pinfunction "DDR_DQ[22]_W19") (pintype "bidirectional"))
    )
    (net (code "329") (name "unconnected-(Lassye3B-DDR_DQ[23]-PadV18)") (class "Default")
      (node (ref "Lassye3") (pin "V18") (pinfunction "DDR_DQ[23]_V18") (pintype "bidirectional"))
    )
    (net (code "330") (name "unconnected-(Lassye3B-DDR_DQ[24]-PadY21)") (class "Default")
      (node (ref "Lassye3") (pin "Y21") (pinfunction "DDR_DQ[24]_Y21") (pintype "bidirectional"))
    )
    (net (code "331") (name "unconnected-(Lassye3B-DDR_DQ[25]-PadY22)") (class "Default")
      (node (ref "Lassye3") (pin "Y22") (pinfunction "DDR_DQ[25]_Y22") (pintype "bidirectional"))
    )
    (net (code "332") (name "unconnected-(Lassye3B-DDR_DQ[26]-PadAA20)") (class "Default")
      (node (ref "Lassye3") (pin "AA20") (pinfunction "DDR_DQ[26]_AA20") (pintype "bidirectional"))
    )
    (net (code "333") (name "unconnected-(Lassye3B-DDR_DQ[27]-PadAA22)") (class "Default")
      (node (ref "Lassye3") (pin "AA22") (pinfunction "DDR_DQ[27]_AA22") (pintype "bidirectional"))
    )
    (net (code "334") (name "unconnected-(Lassye3B-DDR_DQ[28]-PadAB19)") (class "Default")
      (node (ref "Lassye3") (pin "AB19") (pinfunction "DDR_DQ[28]_AB19") (pintype "bidirectional"))
    )
    (net (code "335") (name "unconnected-(Lassye3B-DDR_DQ[29]-PadY18)") (class "Default")
      (node (ref "Lassye3") (pin "Y18") (pinfunction "DDR_DQ[29]_Y18") (pintype "bidirectional"))
    )
    (net (code "336") (name "unconnected-(Lassye3B-DDR_DQ[30]-PadAB18)") (class "Default")
      (node (ref "Lassye3") (pin "AB18") (pinfunction "DDR_DQ[30]_AB18") (pintype "bidirectional"))
    )
    (net (code "337") (name "unconnected-(Lassye3B-DDR_DQ[31]-PadAA18)") (class "Default")
      (node (ref "Lassye3") (pin "AA18") (pinfunction "DDR_DQ[31]_AA18") (pintype "bidirectional"))
    )
    (net (code "338") (name "unconnected-(Lassye3B-DDR_ZQ-PadP18)") (class "Default")
      (node (ref "Lassye3") (pin "P18") (pinfunction "DDR_ZQ_P18") (pintype "bidirectional"))
    )
    (net (code "339") (name "unconnected-(Lassye3C-GPIOB_RXN15-PadR13)") (class "Default")
      (node (ref "Lassye3") (pin "R13") (pinfunction "GPIOB_RXN15_R13") (pintype "bidirectional"))
    )
    (net (code "340") (name "unconnected-(Lassye3C-GPIOB_RXP15-PadR14)") (class "Default")
      (node (ref "Lassye3") (pin "R14") (pinfunction "GPIOB_RXP15_R14") (pintype "bidirectional"))
    )
    (net (code "341") (name "unconnected-(Lassye3C-GPIOB_TXP03_CDI31-PadY4)") (class "Default")
      (node (ref "Lassye3") (pin "Y4") (pinfunction "GPIOB_TXP03_CDI31_Y4") (pintype "bidirectional"))
    )
    (net (code "342") (name "unconnected-(Lassye3C-GPIOL_05_CSO-PadU5)") (class "Default")
      (node (ref "Lassye3") (pin "U5") (pinfunction "GPIOL_05_CSO_U5") (pintype "bidirectional+no_connect"))
    )
    (net (code "343") (name "unconnected-(Lassye3E-REF_RES_2A-PadC5)") (class "Default")
      (node (ref "Lassye3") (pin "C5") (pinfunction "REF_RES_2A_C5") (pintype "bidirectional"))
    )
    (net (code "344") (name "unconnected-(Lassye3E-REF_RES_2B-PadD8)") (class "Default")
      (node (ref "Lassye3") (pin "D8") (pinfunction "REF_RES_2B_D8") (pintype "bidirectional"))
    )
    (net (code "345") (name "unconnected-(Lassye3E-REF_RES_2C-PadC10)") (class "Default")
      (node (ref "Lassye3") (pin "C10") (pinfunction "REF_RES_2C_C10") (pintype "bidirectional"))
    )
    (net (code "346") (name "unconnected-(Lassye3E-REF_RES_4D-PadY10)") (class "Default")
      (node (ref "Lassye3") (pin "Y10") (pinfunction "REF_RES_4D_Y10") (pintype "bidirectional"))
    )
    (net (code "347") (name "unconnected-(Lassye3E-REF_RES_4E-PadW6)") (class "Default")
      (node (ref "Lassye3") (pin "W6") (pinfunction "REF_RES_4E_W6") (pintype "bidirectional"))
    )
    (net (code "348") (name "unconnected-(Lassye3E-REF_RES_4F-PadAA3)") (class "Default")
      (node (ref "Lassye3") (pin "AA3") (pinfunction "REF_RES_4F_AA3") (pintype "bidirectional"))
    )
    (net (code "349") (name "unconnected-(Lassye3F-VCCIO_DDR-PadAA17)") (class "Default")
      (node (ref "Lassye3") (pin "AA17") (pinfunction "VCCIO_DDR_AA17") (pintype "power_in"))
    )
    (net (code "350") (name "unconnected-(Lassye3F-VCCIO_DDR-PadAA19)") (class "Default")
      (node (ref "Lassye3") (pin "AA19") (pinfunction "VCCIO_DDR_AA19") (pintype "power_in"))
    )
    (net (code "351") (name "unconnected-(Lassye3F-VCCIO_DDR-PadAA21)") (class "Default")
      (node (ref "Lassye3") (pin "AA21") (pinfunction "VCCIO_DDR_AA21") (pintype "power_in"))
    )
    (net (code "352") (name "unconnected-(Lassye3F-VCCIO_DDR-PadF19)") (class "Default")
      (node (ref "Lassye3") (pin "F19") (pinfunction "VCCIO_DDR_F19") (pintype "power_in"))
    )
    (net (code "353") (name "unconnected-(Lassye3F-VCCIO_DDR-PadF21)") (class "Default")
      (node (ref "Lassye3") (pin "F21") (pinfunction "VCCIO_DDR_F21") (pintype "power_in"))
    )
    (net (code "354") (name "unconnected-(Lassye3F-VCCIO_DDR-PadG18)") (class "Default")
      (node (ref "Lassye3") (pin "G18") (pinfunction "VCCIO_DDR_G18") (pintype "power_in"))
    )
    (net (code "355") (name "unconnected-(Lassye3F-VCCIO_DDR-PadJ17)") (class "Default")
      (node (ref "Lassye3") (pin "J17") (pinfunction "VCCIO_DDR_J17") (pintype "power_in"))
    )
    (net (code "356") (name "unconnected-(Lassye3F-VCCIO_DDR-PadJ19)") (class "Default")
      (node (ref "Lassye3") (pin "J19") (pinfunction "VCCIO_DDR_J19") (pintype "power_in"))
    )
    (net (code "357") (name "unconnected-(Lassye3F-VCCIO_DDR-PadJ21)") (class "Default")
      (node (ref "Lassye3") (pin "J21") (pinfunction "VCCIO_DDR_J21") (pintype "power_in"))
    )
    (net (code "358") (name "unconnected-(Lassye3F-VCCIO_DDR-PadM17)") (class "Default")
      (node (ref "Lassye3") (pin "M17") (pinfunction "VCCIO_DDR_M17") (pintype "power_in"))
    )
    (net (code "359") (name "unconnected-(Lassye3F-VCCIO_DDR-PadM19)") (class "Default")
      (node (ref "Lassye3") (pin "M19") (pinfunction "VCCIO_DDR_M19") (pintype "power_in"))
    )
    (net (code "360") (name "unconnected-(Lassye3F-VCCIO_DDR-PadM21)") (class "Default")
      (node (ref "Lassye3") (pin "M21") (pinfunction "VCCIO_DDR_M21") (pintype "power_in"))
    )
    (net (code "361") (name "unconnected-(Lassye3F-VCCIO_DDR-PadR17)") (class "Default")
      (node (ref "Lassye3") (pin "R17") (pinfunction "VCCIO_DDR_R17") (pintype "power_in"))
    )
    (net (code "362") (name "unconnected-(Lassye3F-VCCIO_DDR-PadR19)") (class "Default")
      (node (ref "Lassye3") (pin "R19") (pinfunction "VCCIO_DDR_R19") (pintype "power_in"))
    )
    (net (code "363") (name "unconnected-(Lassye3F-VCCIO_DDR-PadR21)") (class "Default")
      (node (ref "Lassye3") (pin "R21") (pinfunction "VCCIO_DDR_R21") (pintype "power_in"))
    )
    (net (code "364") (name "unconnected-(Lassye3F-VCCIO_DDR-PadV17)") (class "Default")
      (node (ref "Lassye3") (pin "V17") (pinfunction "VCCIO_DDR_V17") (pintype "power_in"))
    )
    (net (code "365") (name "unconnected-(Lassye3F-VCCIO_DDR-PadV19)") (class "Default")
      (node (ref "Lassye3") (pin "V19") (pinfunction "VCCIO_DDR_V19") (pintype "power_in"))
    )
    (net (code "366") (name "unconnected-(Lassye3F-VCCIO_DDR-PadV21)") (class "Default")
      (node (ref "Lassye3") (pin "V21") (pinfunction "VCCIO_DDR_V21") (pintype "power_in"))
    )
  )
)
